# reaction_wheel_board.net
KiCad netlist of a schematic drawn in EAGLE
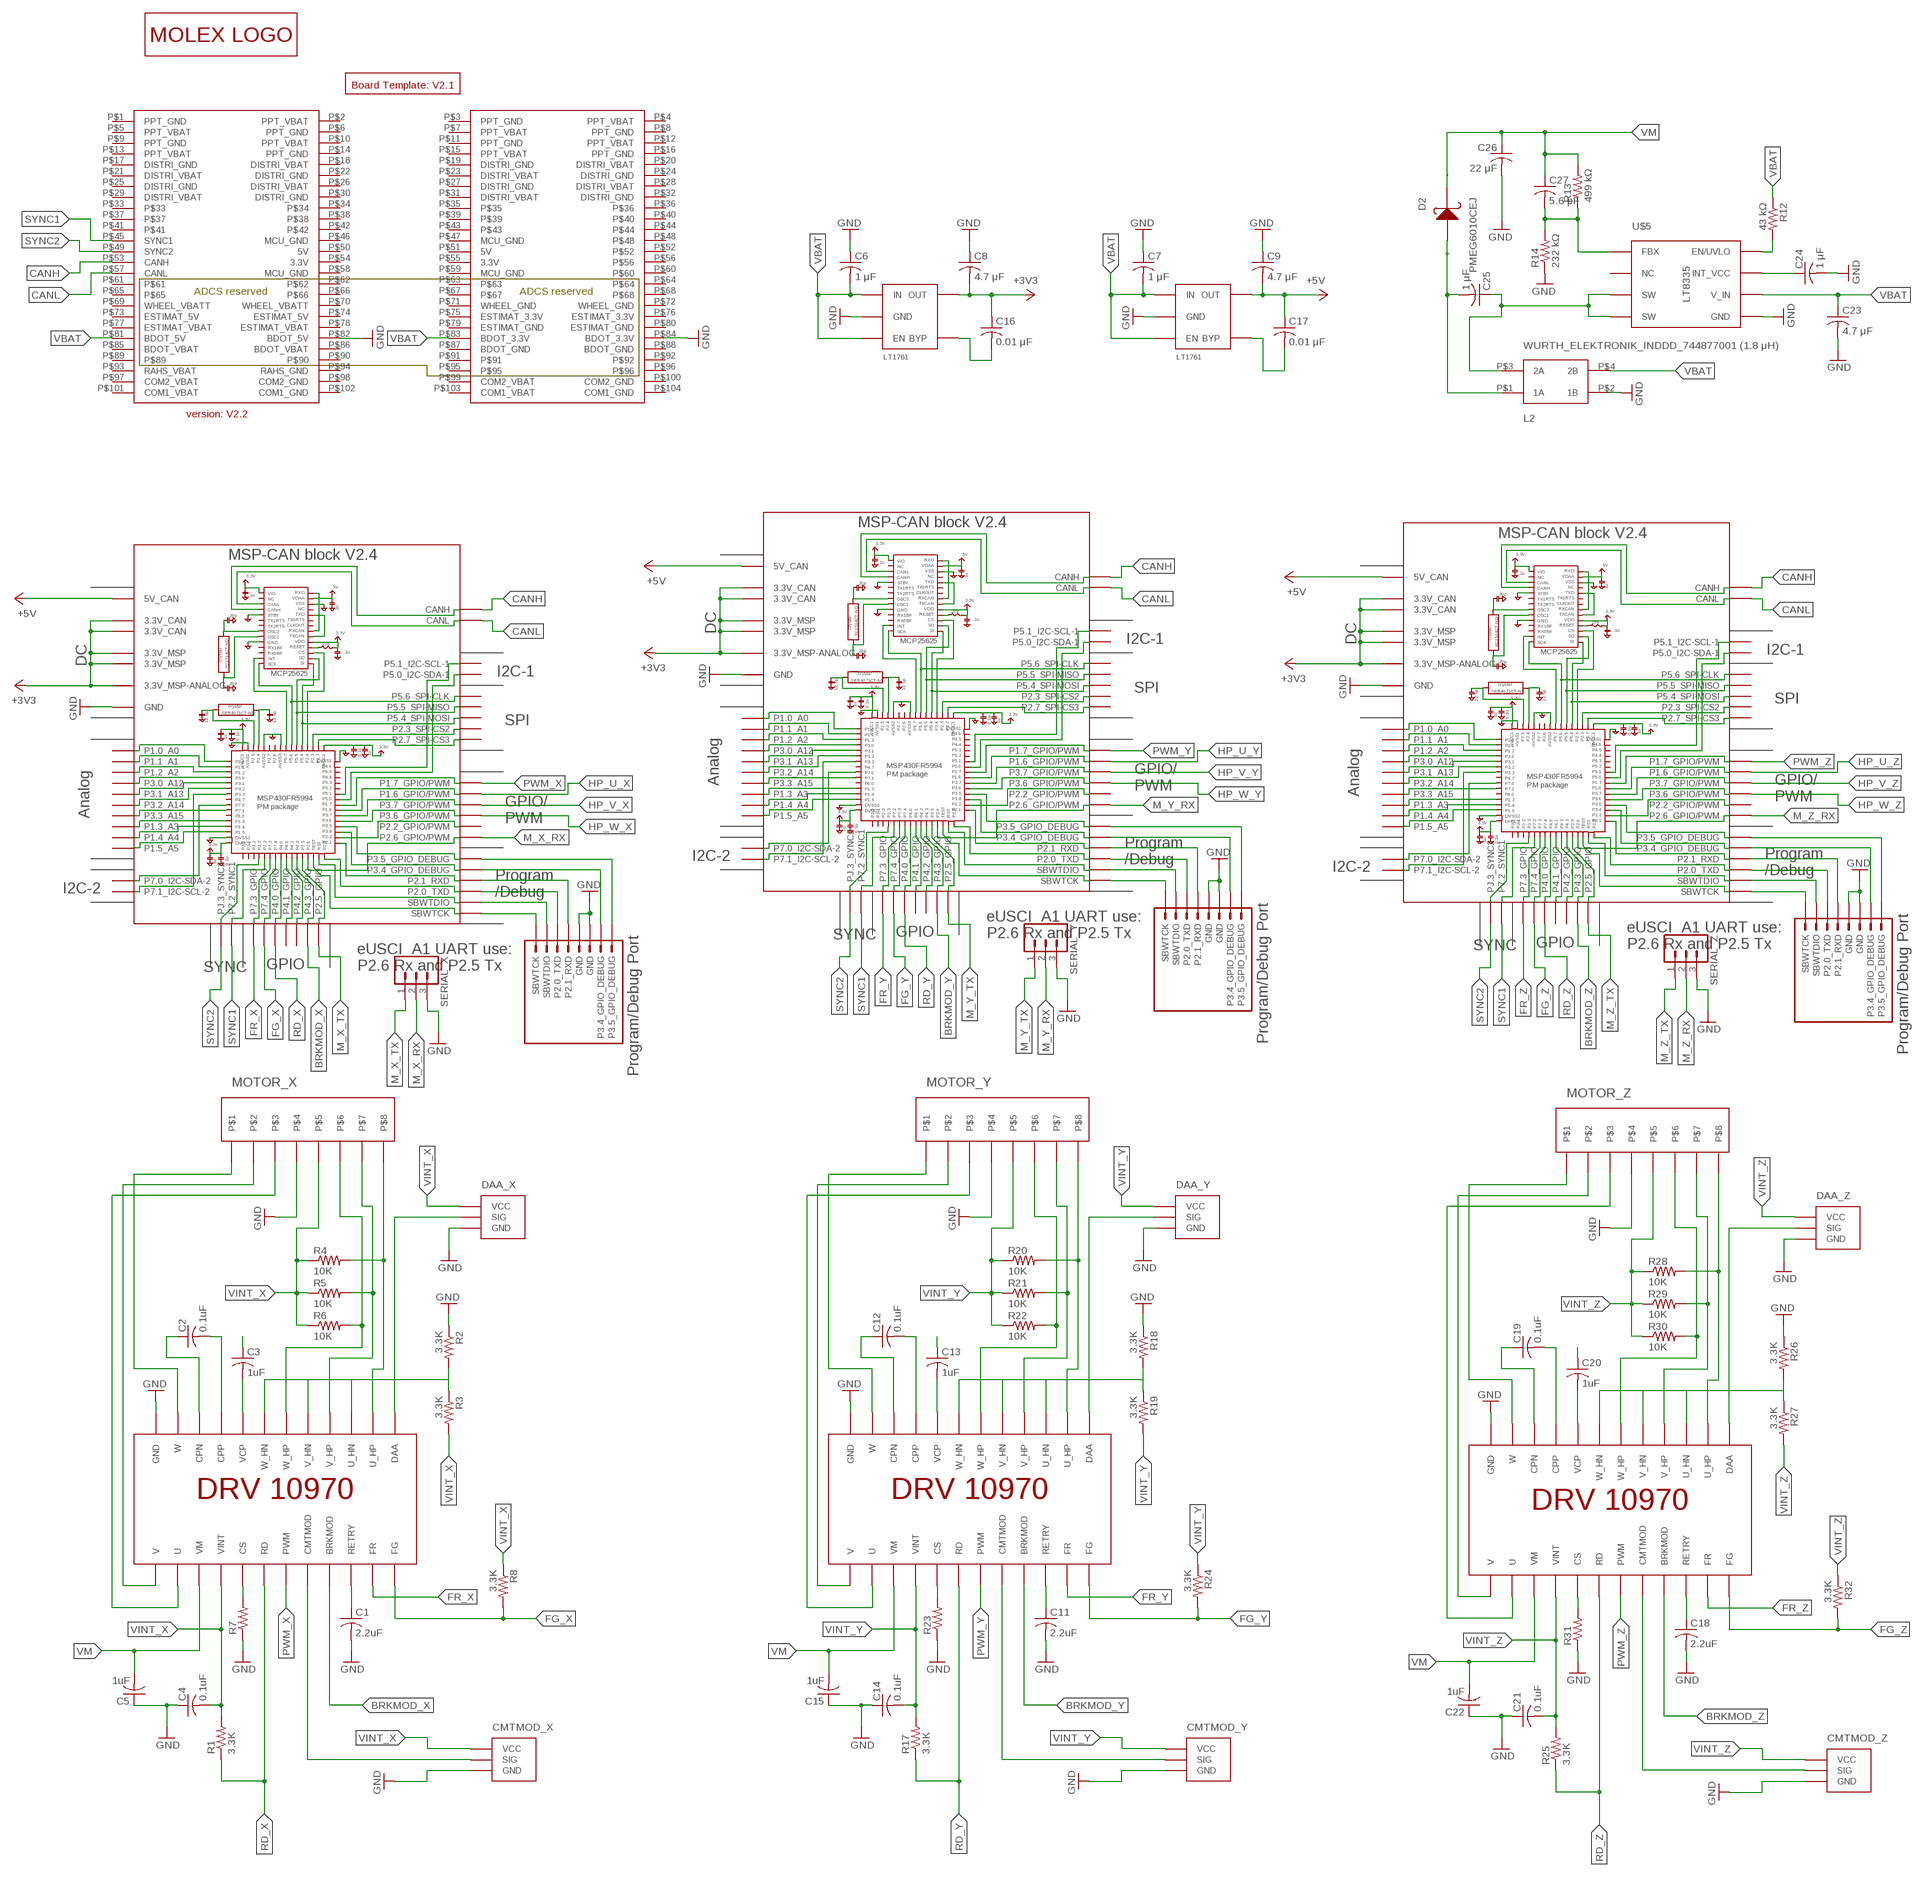
[diagram p0: schematic, sheet 1]

(export (version "E")
  (design (tool "Eeschema 10.0.6"))
  (components
    (comp (ref "C1")
      (value "2.2uF")
      (footprint "eagle-import:C1206")
      (libsource (lib "eagle-import") (part "C-USC1206"))
    )
    (comp (ref "C2")
      (value "0.1uF")
      (footprint "eagle-import:C0805")
      (libsource (lib "eagle-import") (part "C-USC0805"))
    )
    (comp (ref "C3")
      (value "1uF")
      (footprint "eagle-import:C1206")
      (libsource (lib "eagle-import") (part "C-USC1206"))
    )
    (comp (ref "C4")
      (value "0.1uF")
      (footprint "eagle-import:C0805")
      (libsource (lib "eagle-import") (part "C-USC0805"))
    )
    (comp (ref "C5")
      (value "1uF")
      (footprint "eagle-import:C1206")
      (libsource (lib "eagle-import") (part "C-USC1206"))
    )
    (comp (ref "C6")
      (value "1 μF")
      (footprint "eagle-import:C0805")
      (libsource (lib "eagle-import") (part "C-USC0805"))
    )
    (comp (ref "C7")
      (value "1 μF")
      (footprint "eagle-import:C0805")
      (libsource (lib "eagle-import") (part "C-USC0805"))
    )
    (comp (ref "C8")
      (value "4.7 μF")
      (footprint "eagle-import:C0805")
      (libsource (lib "eagle-import") (part "C-USC0805"))
    )
    (comp (ref "C9")
      (value "4.7 μF")
      (footprint "eagle-import:C0805")
      (libsource (lib "eagle-import") (part "C-USC0805"))
    )
    (comp (ref "C11")
      (value "2.2uF")
      (footprint "eagle-import:C1206")
      (libsource (lib "eagle-import") (part "C-USC1206"))
    )
    (comp (ref "C12")
      (value "0.1uF")
      (footprint "eagle-import:C0805")
      (libsource (lib "eagle-import") (part "C-USC0805"))
    )
    (comp (ref "C13")
      (value "1uF")
      (footprint "eagle-import:C1206")
      (libsource (lib "eagle-import") (part "C-USC1206"))
    )
    (comp (ref "C14")
      (value "0.1uF")
      (footprint "eagle-import:C0805")
      (libsource (lib "eagle-import") (part "C-USC0805"))
    )
    (comp (ref "C15")
      (value "1uF")
      (footprint "eagle-import:C1206")
      (libsource (lib "eagle-import") (part "C-USC1206"))
    )
    (comp (ref "C16")
      (value "0.01 μF")
      (footprint "eagle-import:C0805")
      (libsource (lib "eagle-import") (part "C-USC0805"))
    )
    (comp (ref "C17")
      (value "0.01 μF")
      (footprint "eagle-import:C0805")
      (libsource (lib "eagle-import") (part "C-USC0805"))
    )
    (comp (ref "C18")
      (value "2.2uF")
      (footprint "eagle-import:C1206")
      (libsource (lib "eagle-import") (part "C-USC1206"))
    )
    (comp (ref "C19")
      (value "0.1uF")
      (footprint "eagle-import:C0805")
      (libsource (lib "eagle-import") (part "C-USC0805"))
    )
    (comp (ref "C20")
      (value "1uF")
      (footprint "eagle-import:C1206")
      (libsource (lib "eagle-import") (part "C-USC1206"))
    )
    (comp (ref "C21")
      (value "0.1uF")
      (footprint "eagle-import:C0805")
      (libsource (lib "eagle-import") (part "C-USC0805"))
    )
    (comp (ref "C22")
      (value "1uF")
      (footprint "eagle-import:C1206")
      (libsource (lib "eagle-import") (part "C-USC1206"))
    )
    (comp (ref "C23")
      (value "4.7 μF")
      (footprint "eagle-import:C0805")
      (libsource (lib "eagle-import") (part "C-USC0805"))
    )
    (comp (ref "C24")
      (value "1 μF")
      (footprint "eagle-import:C0805")
      (libsource (lib "eagle-import") (part "C-USC0805"))
    )
    (comp (ref "C25")
      (value "1 μF")
      (footprint "eagle-import:C0805")
      (libsource (lib "eagle-import") (part "C-USC0805"))
    )
    (comp (ref "C26")
      (value "22 μF")
      (footprint "eagle-import:C0805")
      (libsource (lib "eagle-import") (part "C-USC0805"))
    )
    (comp (ref "C27")
      (value "5.6 pF")
      (footprint "eagle-import:C0805")
      (libsource (lib "eagle-import") (part "C-USC0805"))
    )
    (comp (ref "CMTMOD_X")
      (value "0_OHM_JUMPER")
      (footprint "eagle-import:0_OHM_JUMPER")
      (libsource (lib "eagle-import") (part "0_OHM_JUMPER"))
    )
    (comp (ref "CMTMOD_Y")
      (value "0_OHM_JUMPER")
      (footprint "eagle-import:0_OHM_JUMPER")
      (libsource (lib "eagle-import") (part "0_OHM_JUMPER"))
    )
    (comp (ref "CMTMOD_Z")
      (value "0_OHM_JUMPER")
      (footprint "eagle-import:0_OHM_JUMPER")
      (libsource (lib "eagle-import") (part "0_OHM_JUMPER"))
    )
    (comp (ref "D2")
      (value "PMEG6010CEJ")
      (footprint "eagle-import:SC-90")
      (libsource (lib "eagle-import") (part "PMEG6010CEJ"))
    )
    (comp (ref "DAA_X")
      (value "0_OHM_JUMPER")
      (footprint "eagle-import:0_OHM_JUMPER")
      (libsource (lib "eagle-import") (part "0_OHM_JUMPER"))
    )
    (comp (ref "DAA_Y")
      (value "0_OHM_JUMPER")
      (footprint "eagle-import:0_OHM_JUMPER")
      (libsource (lib "eagle-import") (part "0_OHM_JUMPER"))
    )
    (comp (ref "DAA_Z")
      (value "0_OHM_JUMPER")
      (footprint "eagle-import:0_OHM_JUMPER")
      (libsource (lib "eagle-import") (part "0_OHM_JUMPER"))
    )
    (comp (ref "L2")
      (value "WURTH_ELEKTRONIK_INDDD_744877001 (1.8 μH)")
      (footprint "eagle-import:WURTH_ELEKTRONIK_INDDD_744877001")
      (libsource (lib "eagle-import") (part "WURTH_ELEKTRONIK_INDDD_744877001"))
    )
    (comp (ref "LDO_3V3")
      (value "LINEAR_LDO_LT1761-X")
      (footprint "eagle-import:SOT-23-5")
      (libsource (lib "eagle-import") (part "LINEAR_LDO_LT1761-X"))
    )
    (comp (ref "LDO_5V")
      (value "LINEAR_LDO_LT1761-X")
      (footprint "eagle-import:SOT-23-5")
      (libsource (lib "eagle-import") (part "LINEAR_LDO_LT1761-X"))
    )
    (comp (ref "MOTOR_X")
      (value "PICOLOCK_8")
      (footprint "eagle-import:PICOLOCK_8")
      (libsource (lib "eagle-import") (part "PICOLOCK_8"))
    )
    (comp (ref "MOTOR_Y")
      (value "PICOLOCK_8")
      (footprint "eagle-import:PICOLOCK_8")
      (libsource (lib "eagle-import") (part "PICOLOCK_8"))
    )
    (comp (ref "MOTOR_Z")
      (value "PICOLOCK_8")
      (footprint "eagle-import:PICOLOCK_8")
      (libsource (lib "eagle-import") (part "PICOLOCK_8"))
    )
    (comp (ref "R1")
      (value "3.3K")
      (footprint "eagle-import:R0805")
      (libsource (lib "eagle-import") (part "R-US_R0805"))
    )
    (comp (ref "R2")
      (value "3.3K")
      (footprint "eagle-import:R0805")
      (libsource (lib "eagle-import") (part "R-US_R0805"))
    )
    (comp (ref "R3")
      (value "3.3K")
      (footprint "eagle-import:R0805")
      (libsource (lib "eagle-import") (part "R-US_R0805"))
    )
    (comp (ref "R4")
      (value "10K")
      (footprint "eagle-import:R0805")
      (libsource (lib "eagle-import") (part "R-US_R0805"))
    )
    (comp (ref "R5")
      (value "10K")
      (footprint "eagle-import:R0805")
      (libsource (lib "eagle-import") (part "R-US_R0805"))
    )
    (comp (ref "R6")
      (value "10K")
      (footprint "eagle-import:R0805")
      (libsource (lib "eagle-import") (part "R-US_R0805"))
    )
    (comp (ref "R7")
      (value "R-US_R0805")
      (footprint "eagle-import:R0805")
      (libsource (lib "eagle-import") (part "R-US_R0805"))
    )
    (comp (ref "R8")
      (value "3.3K")
      (footprint "eagle-import:R0805")
      (libsource (lib "eagle-import") (part "R-US_R0805"))
    )
    (comp (ref "R12")
      (value "43 kΩ")
      (footprint "eagle-import:R0805")
      (libsource (lib "eagle-import") (part "R-US_R0805"))
    )
    (comp (ref "R13")
      (value "499 kΩ")
      (footprint "eagle-import:R0805")
      (libsource (lib "eagle-import") (part "R-US_R0805"))
    )
    (comp (ref "R14")
      (value "232 kΩ")
      (footprint "eagle-import:R0805")
      (libsource (lib "eagle-import") (part "R-US_R0805"))
    )
    (comp (ref "R17")
      (value "3.3K")
      (footprint "eagle-import:R0805")
      (libsource (lib "eagle-import") (part "R-US_R0805"))
    )
    (comp (ref "R18")
      (value "3.3K")
      (footprint "eagle-import:R0805")
      (libsource (lib "eagle-import") (part "R-US_R0805"))
    )
    (comp (ref "R19")
      (value "3.3K")
      (footprint "eagle-import:R0805")
      (libsource (lib "eagle-import") (part "R-US_R0805"))
    )
    (comp (ref "R20")
      (value "10K")
      (footprint "eagle-import:R0805")
      (libsource (lib "eagle-import") (part "R-US_R0805"))
    )
    (comp (ref "R21")
      (value "10K")
      (footprint "eagle-import:R0805")
      (libsource (lib "eagle-import") (part "R-US_R0805"))
    )
    (comp (ref "R22")
      (value "10K")
      (footprint "eagle-import:R0805")
      (libsource (lib "eagle-import") (part "R-US_R0805"))
    )
    (comp (ref "R23")
      (value "R-US_R0805")
      (footprint "eagle-import:R0805")
      (libsource (lib "eagle-import") (part "R-US_R0805"))
    )
    (comp (ref "R24")
      (value "3.3K")
      (footprint "eagle-import:R0805")
      (libsource (lib "eagle-import") (part "R-US_R0805"))
    )
    (comp (ref "R25")
      (value "3.3K")
      (footprint "eagle-import:R0805")
      (libsource (lib "eagle-import") (part "R-US_R0805"))
    )
    (comp (ref "R26")
      (value "3.3K")
      (footprint "eagle-import:R0805")
      (libsource (lib "eagle-import") (part "R-US_R0805"))
    )
    (comp (ref "R27")
      (value "3.3K")
      (footprint "eagle-import:R0805")
      (libsource (lib "eagle-import") (part "R-US_R0805"))
    )
    (comp (ref "R28")
      (value "10K")
      (footprint "eagle-import:R0805")
      (libsource (lib "eagle-import") (part "R-US_R0805"))
    )
    (comp (ref "R29")
      (value "10K")
      (footprint "eagle-import:R0805")
      (libsource (lib "eagle-import") (part "R-US_R0805"))
    )
    (comp (ref "R30")
      (value "10K")
      (footprint "eagle-import:R0805")
      (libsource (lib "eagle-import") (part "R-US_R0805"))
    )
    (comp (ref "R31")
      (value "R-US_R0805")
      (footprint "eagle-import:R0805")
      (libsource (lib "eagle-import") (part "R-US_R0805"))
    )
    (comp (ref "R32")
      (value "3.3K")
      (footprint "eagle-import:R0805")
      (libsource (lib "eagle-import") (part "R-US_R0805"))
    )
    (comp (ref "SERIAL_X")
      (value "CONN_03LOCK")
      (footprint "eagle-import:1X03_LOCK")
      (libsource (lib "eagle-import") (part "CONN_03LOCK"))
    )
    (comp (ref "SERIAL_Y")
      (value "CONN_03LOCK")
      (footprint "eagle-import:1X03_LOCK")
      (libsource (lib "eagle-import") (part "CONN_03LOCK"))
    )
    (comp (ref "SERIAL_Z")
      (value "CONN_03LOCK")
      (footprint "eagle-import:1X03_LOCK")
      (libsource (lib "eagle-import") (part "CONN_03LOCK"))
    )
    (comp (ref "U$1")
      (value "BOARD_TEMPLATE")
      (footprint "eagle-import:BOARD_TEMPLATE")
      (libsource (lib "eagle-import") (part "BOARD_TEMPLATE"))
    )
    (comp (ref "U$2")
      (value "PC104_CONNECTOR")
      (footprint "eagle-import:PC104_CONNECTOR")
      (libsource (lib "eagle-import") (part "PC104_CONNECTOR"))
    )
    (comp (ref "U$3")
      (value "MSP-CAN_BLOCK")
      (footprint "eagle-import:MSP-CAN_BLOCK")
      (libsource (lib "eagle-import") (part "MSP-CAN_BLOCK"))
    )
    (comp (ref "U$4")
      (value "PROGRAM/DEBUG_PORT")
      (footprint "eagle-import:1X08_CONNECTOR")
      (libsource (lib "eagle-import") (part "PROGRAM/DEBUG_PORT"))
    )
    (comp (ref "U$5")
      (value "LT8335")
      (footprint "eagle-import:DDB")
      (libsource (lib "eagle-import") (part "LT8335"))
    )
    (comp (ref "U$7")
      (value "DRV10970")
      (footprint "eagle-import:DRV10970")
      (libsource (lib "eagle-import") (part "DRV10970"))
    )
    (comp (ref "U$8")
      (value "LOGO_MOLEX")
      (footprint "eagle-import:LOGO_MOLEX")
      (libsource (lib "eagle-import") (part "LOGO_MOLEX"))
    )
    (comp (ref "U$10")
      (value "MSP-CAN_BLOCK")
      (footprint "eagle-import:MSP-CAN_BLOCK")
      (libsource (lib "eagle-import") (part "MSP-CAN_BLOCK"))
    )
    (comp (ref "U$11")
      (value "PROGRAM/DEBUG_PORT")
      (footprint "eagle-import:1X08_CONNECTOR")
      (libsource (lib "eagle-import") (part "PROGRAM/DEBUG_PORT"))
    )
    (comp (ref "U$12")
      (value "DRV10970")
      (footprint "eagle-import:DRV10970")
      (libsource (lib "eagle-import") (part "DRV10970"))
    )
    (comp (ref "U$13")
      (value "MSP-CAN_BLOCK")
      (footprint "eagle-import:MSP-CAN_BLOCK")
      (libsource (lib "eagle-import") (part "MSP-CAN_BLOCK"))
    )
    (comp (ref "U$14")
      (value "PROGRAM/DEBUG_PORT")
      (footprint "eagle-import:1X08_CONNECTOR")
      (libsource (lib "eagle-import") (part "PROGRAM/DEBUG_PORT"))
    )
    (comp (ref "U$15")
      (value "DRV10970")
      (footprint "eagle-import:DRV10970")
      (libsource (lib "eagle-import") (part "DRV10970"))
    )
  )
  (nets
    (net (code "1") (name "+3V3") (class "Default")
      (node (ref "C16") (pin "1") (pinfunction "1_1") (pintype "passive"))
      (node (ref "C8") (pin "2") (pinfunction "2_2") (pintype "passive"))
      (node (ref "LDO_3V3") (pin "P$5") (pinfunction "OUT_P$5") (pintype "bidirectional"))
      (node (ref "U$10") (pin "3.3V@CAN1") (pinfunction "3.3V_CAN_3.3V@CAN1") (pintype "bidirectional"))
      (node (ref "U$10") (pin "3.3V@CAN2") (pinfunction "3.3V_CAN_3.3V@CAN2") (pintype "bidirectional"))
      (node (ref "U$10") (pin "3.3V@MSP1") (pinfunction "3.3V_MSP_3.3V@MSP1") (pintype "bidirectional"))
      (node (ref "U$10") (pin "3.3V@MSP2") (pinfunction "3.3V_MSP_3.3V@MSP2") (pintype "bidirectional"))
      (node (ref "U$10") (pin "3.3V_ANALOG@MSP2") (pinfunction "3.3V_MSP-ANALOG_3.3V_ANALOG@MSP2") (pintype "bidirectional"))
      (node (ref "U$13") (pin "3.3V@CAN1") (pinfunction "3.3V_CAN_3.3V@CAN1") (pintype "bidirectional"))
      (node (ref "U$13") (pin "3.3V@CAN2") (pinfunction "3.3V_CAN_3.3V@CAN2") (pintype "bidirectional"))
      (node (ref "U$13") (pin "3.3V@MSP1") (pinfunction "3.3V_MSP_3.3V@MSP1") (pintype "bidirectional"))
      (node (ref "U$13") (pin "3.3V@MSP2") (pinfunction "3.3V_MSP_3.3V@MSP2") (pintype "bidirectional"))
      (node (ref "U$13") (pin "3.3V_ANALOG@MSP2") (pinfunction "3.3V_MSP-ANALOG_3.3V_ANALOG@MSP2") (pintype "bidirectional"))
      (node (ref "U$3") (pin "3.3V@CAN1") (pinfunction "3.3V_CAN_3.3V@CAN1") (pintype "bidirectional"))
      (node (ref "U$3") (pin "3.3V@CAN2") (pinfunction "3.3V_CAN_3.3V@CAN2") (pintype "bidirectional"))
      (node (ref "U$3") (pin "3.3V@MSP1") (pinfunction "3.3V_MSP_3.3V@MSP1") (pintype "bidirectional"))
      (node (ref "U$3") (pin "3.3V@MSP2") (pinfunction "3.3V_MSP_3.3V@MSP2") (pintype "bidirectional"))
      (node (ref "U$3") (pin "3.3V_ANALOG@MSP2") (pinfunction "3.3V_MSP-ANALOG_3.3V_ANALOG@MSP2") (pintype "bidirectional"))
    )
    (net (code "2") (name "+5V") (class "Default")
      (node (ref "C17") (pin "1") (pinfunction "1_1") (pintype "passive"))
      (node (ref "C9") (pin "2") (pinfunction "2_2") (pintype "passive"))
      (node (ref "LDO_5V") (pin "P$5") (pinfunction "OUT_P$5") (pintype "bidirectional"))
      (node (ref "U$10") (pin "5V") (pinfunction "5V_CAN_5V") (pintype "bidirectional"))
      (node (ref "U$13") (pin "5V") (pinfunction "5V_CAN_5V") (pintype "bidirectional"))
      (node (ref "U$3") (pin "5V") (pinfunction "5V_CAN_5V") (pintype "bidirectional"))
    )
    (net (code "3") (name "BRKMOD_X") (class "Default")
      (node (ref "U$3") (pin "P4.3_GPIO") (pinfunction "P4.3_GPIO_P4.3_GPIO") (pintype "bidirectional"))
      (node (ref "U$7") (pin "BRKMOD") (pinfunction "BRKMOD_BRKMOD") (pintype "bidirectional"))
    )
    (net (code "4") (name "BRKMOD_Y") (class "Default")
      (node (ref "U$10") (pin "P4.3_GPIO") (pinfunction "P4.3_GPIO_P4.3_GPIO") (pintype "bidirectional"))
      (node (ref "U$12") (pin "BRKMOD") (pinfunction "BRKMOD_BRKMOD") (pintype "bidirectional"))
    )
    (net (code "5") (name "BRKMOD_Z") (class "Default")
      (node (ref "U$13") (pin "P4.3_GPIO") (pinfunction "P4.3_GPIO_P4.3_GPIO") (pintype "bidirectional"))
      (node (ref "U$15") (pin "BRKMOD") (pinfunction "BRKMOD_BRKMOD") (pintype "bidirectional"))
    )
    (net (code "6") (name "CANH") (class "Default")
      (node (ref "U$10") (pin "CANH") (pinfunction "CANH_CANH") (pintype "bidirectional"))
      (node (ref "U$13") (pin "CANH") (pinfunction "CANH_CANH") (pintype "bidirectional"))
      (node (ref "U$2") (pin "P$53") (pinfunction "CANH_P$53") (pintype "bidirectional"))
      (node (ref "U$3") (pin "CANH") (pinfunction "CANH_CANH") (pintype "bidirectional"))
    )
    (net (code "7") (name "CANL") (class "Default")
      (node (ref "U$10") (pin "CANL") (pinfunction "CANL_CANL") (pintype "bidirectional"))
      (node (ref "U$13") (pin "CANL") (pinfunction "CANL_CANL") (pintype "bidirectional"))
      (node (ref "U$2") (pin "P$57") (pinfunction "CANL_P$57") (pintype "bidirectional"))
      (node (ref "U$3") (pin "CANL") (pinfunction "CANL_CANL") (pintype "bidirectional"))
    )
    (net (code "8") (name "FG_X") (class "Default")
      (node (ref "R8") (pin "2") (pinfunction "2_2") (pintype "passive"))
      (node (ref "U$3") (pin "P7.4_GPIO") (pinfunction "P7.4_GPIO_P7.4_GPIO") (pintype "bidirectional"))
      (node (ref "U$7") (pin "FG") (pinfunction "FG_FG") (pintype "bidirectional"))
    )
    (net (code "9") (name "FG_Y") (class "Default")
      (node (ref "R24") (pin "2") (pinfunction "2_2") (pintype "passive"))
      (node (ref "U$10") (pin "P7.4_GPIO") (pinfunction "P7.4_GPIO_P7.4_GPIO") (pintype "bidirectional"))
      (node (ref "U$12") (pin "FG") (pinfunction "FG_FG") (pintype "bidirectional"))
    )
    (net (code "10") (name "FG_Z") (class "Default")
      (node (ref "R32") (pin "2") (pinfunction "2_2") (pintype "passive"))
      (node (ref "U$13") (pin "P7.4_GPIO") (pinfunction "P7.4_GPIO_P7.4_GPIO") (pintype "bidirectional"))
      (node (ref "U$15") (pin "FG") (pinfunction "FG_FG") (pintype "bidirectional"))
    )
    (net (code "11") (name "FR_X") (class "Default")
      (node (ref "U$3") (pin "P7.3_GPIO") (pinfunction "P7.3_GPIO_P7.3_GPIO") (pintype "bidirectional"))
      (node (ref "U$7") (pin "FR") (pinfunction "FR_FR") (pintype "bidirectional"))
    )
    (net (code "12") (name "FR_Y") (class "Default")
      (node (ref "U$10") (pin "P7.3_GPIO") (pinfunction "P7.3_GPIO_P7.3_GPIO") (pintype "bidirectional"))
      (node (ref "U$12") (pin "FR") (pinfunction "FR_FR") (pintype "bidirectional"))
    )
    (net (code "13") (name "FR_Z") (class "Default")
      (node (ref "U$13") (pin "P7.3_GPIO") (pinfunction "P7.3_GPIO_P7.3_GPIO") (pintype "bidirectional"))
      (node (ref "U$15") (pin "FR") (pinfunction "FR_FR") (pintype "bidirectional"))
    )
    (net (code "14") (name "GND") (class "Default")
      (node (ref "C1") (pin "2") (pinfunction "2_2") (pintype "passive"))
      (node (ref "C11") (pin "2") (pinfunction "2_2") (pintype "passive"))
      (node (ref "C13") (pin "1") (pinfunction "1_1") (pintype "passive"))
      (node (ref "C14") (pin "1") (pinfunction "1_1") (pintype "passive"))
      (node (ref "C15") (pin "1") (pinfunction "1_1") (pintype "passive"))
      (node (ref "C18") (pin "2") (pinfunction "2_2") (pintype "passive"))
      (node (ref "C20") (pin "1") (pinfunction "1_1") (pintype "passive"))
      (node (ref "C21") (pin "1") (pinfunction "1_1") (pintype "passive"))
      (node (ref "C22") (pin "1") (pinfunction "1_1") (pintype "passive"))
      (node (ref "C23") (pin "2") (pinfunction "2_2") (pintype "passive"))
      (node (ref "C24") (pin "2") (pinfunction "2_2") (pintype "passive"))
      (node (ref "C26") (pin "2") (pinfunction "2_2") (pintype "passive"))
      (node (ref "C3") (pin "1") (pinfunction "1_1") (pintype "passive"))
      (node (ref "C4") (pin "1") (pinfunction "1_1") (pintype "passive"))
      (node (ref "C5") (pin "1") (pinfunction "1_1") (pintype "passive"))
      (node (ref "C6") (pin "1") (pinfunction "1_1") (pintype "passive"))
      (node (ref "C7") (pin "1") (pinfunction "1_1") (pintype "passive"))
      (node (ref "C8") (pin "1") (pinfunction "1_1") (pintype "passive"))
      (node (ref "C9") (pin "1") (pinfunction "1_1") (pintype "passive"))
      (node (ref "CMTMOD_X") (pin "P$1") (pinfunction "GND_P$1") (pintype "bidirectional"))
      (node (ref "CMTMOD_Y") (pin "P$1") (pinfunction "GND_P$1") (pintype "bidirectional"))
      (node (ref "CMTMOD_Z") (pin "P$1") (pinfunction "GND_P$1") (pintype "bidirectional"))
      (node (ref "DAA_X") (pin "P$1") (pinfunction "GND_P$1") (pintype "bidirectional"))
      (node (ref "DAA_Y") (pin "P$1") (pinfunction "GND_P$1") (pintype "bidirectional"))
      (node (ref "DAA_Z") (pin "P$1") (pinfunction "GND_P$1") (pintype "bidirectional"))
      (node (ref "L2") (pin "P$2") (pinfunction "1B_P$2") (pintype "bidirectional"))
      (node (ref "LDO_3V3") (pin "P$2") (pinfunction "GND_P$2") (pintype "bidirectional"))
      (node (ref "LDO_5V") (pin "P$2") (pinfunction "GND_P$2") (pintype "bidirectional"))
      (node (ref "MOTOR_X") (pin "P$4") (pinfunction "P$4_P$4") (pintype "bidirectional"))
      (node (ref "MOTOR_Y") (pin "P$4") (pinfunction "P$4_P$4") (pintype "bidirectional"))
      (node (ref "MOTOR_Z") (pin "P$4") (pinfunction "P$4_P$4") (pintype "bidirectional"))
      (node (ref "R14") (pin "1") (pinfunction "1_1") (pintype "passive"))
      (node (ref "R18") (pin "1") (pinfunction "1_1") (pintype "passive"))
      (node (ref "R2") (pin "1") (pinfunction "1_1") (pintype "passive"))
      (node (ref "R23") (pin "1") (pinfunction "1_1") (pintype "passive"))
      (node (ref "R26") (pin "1") (pinfunction "1_1") (pintype "passive"))
      (node (ref "R31") (pin "1") (pinfunction "1_1") (pintype "passive"))
      (node (ref "R7") (pin "1") (pinfunction "1_1") (pintype "passive"))
      (node (ref "SERIAL_X") (pin "3") (pinfunction "3_3") (pintype "passive"))
      (node (ref "SERIAL_Y") (pin "3") (pinfunction "3_3") (pintype "passive"))
      (node (ref "SERIAL_Z") (pin "3") (pinfunction "3_3") (pintype "passive"))
      (node (ref "U$10") (pin "GND@1") (pinfunction "GND_GND@1") (pintype "bidirectional"))
      (node (ref "U$10") (pin "GND@10") (pinfunction "GND_GND@10") (pintype "bidirectional"))
      (node (ref "U$10") (pin "GND@11") (pinfunction "GND_GND@11") (pintype "bidirectional"))
      (node (ref "U$10") (pin "GND@12") (pinfunction "GND_GND@12") (pintype "bidirectional"))
      (node (ref "U$10") (pin "GND@13") (pinfunction "GND_GND@13") (pintype "bidirectional"))
      (node (ref "U$10") (pin "GND@14") (pinfunction "GND_GND@14") (pintype "bidirectional"))
      (node (ref "U$10") (pin "GND@15") (pinfunction "GND_GND@15") (pintype "bidirectional"))
      (node (ref "U$10") (pin "GND@16") (pinfunction "GND_GND@16") (pintype "bidirectional"))
      (node (ref "U$10") (pin "GND@17") (pinfunction "GND_GND@17") (pintype "bidirectional"))
      (node (ref "U$10") (pin "GND@2") (pinfunction "GND_GND@2") (pintype "bidirectional"))
      (node (ref "U$10") (pin "GND@26") (pinfunction "GND_GND@26") (pintype "bidirectional"))
      (node (ref "U$10") (pin "GND@3") (pinfunction "GND_GND@3") (pintype "bidirectional"))
      (node (ref "U$10") (pin "GND@4") (pinfunction "GND_GND@4") (pintype "bidirectional"))
      (node (ref "U$10") (pin "GND@5") (pinfunction "GND_GND@5") (pintype "bidirectional"))
      (node (ref "U$10") (pin "GND@7") (pinfunction "GND_GND@7") (pintype "bidirectional"))
      (node (ref "U$10") (pin "GND@8") (pinfunction "GND_GND@8") (pintype "bidirectional"))
      (node (ref "U$10") (pin "GND@9") (pinfunction "GND_GND@9") (pintype "bidirectional"))
      (node (ref "U$11") (pin "5") (pinfunction "GND_5") (pintype "bidirectional"))
      (node (ref "U$11") (pin "6") (pinfunction "GND_6") (pintype "bidirectional"))
      (node (ref "U$12") (pin "GND@1") (pinfunction "GND_GND@1") (pintype "bidirectional"))
      (node (ref "U$12") (pin "GND@2") (pinfunction "GND_GND@2") (pintype "bidirectional"))
      (node (ref "U$13") (pin "GND@1") (pinfunction "GND_GND@1") (pintype "bidirectional"))
      (node (ref "U$13") (pin "GND@10") (pinfunction "GND_GND@10") (pintype "bidirectional"))
      (node (ref "U$13") (pin "GND@11") (pinfunction "GND_GND@11") (pintype "bidirectional"))
      (node (ref "U$13") (pin "GND@12") (pinfunction "GND_GND@12") (pintype "bidirectional"))
      (node (ref "U$13") (pin "GND@13") (pinfunction "GND_GND@13") (pintype "bidirectional"))
      (node (ref "U$13") (pin "GND@14") (pinfunction "GND_GND@14") (pintype "bidirectional"))
      (node (ref "U$13") (pin "GND@15") (pinfunction "GND_GND@15") (pintype "bidirectional"))
      (node (ref "U$13") (pin "GND@16") (pinfunction "GND_GND@16") (pintype "bidirectional"))
      (node (ref "U$13") (pin "GND@17") (pinfunction "GND_GND@17") (pintype "bidirectional"))
      (node (ref "U$13") (pin "GND@2") (pinfunction "GND_GND@2") (pintype "bidirectional"))
      (node (ref "U$13") (pin "GND@26") (pinfunction "GND_GND@26") (pintype "bidirectional"))
      (node (ref "U$13") (pin "GND@3") (pinfunction "GND_GND@3") (pintype "bidirectional"))
      (node (ref "U$13") (pin "GND@4") (pinfunction "GND_GND@4") (pintype "bidirectional"))
      (node (ref "U$13") (pin "GND@5") (pinfunction "GND_GND@5") (pintype "bidirectional"))
      (node (ref "U$13") (pin "GND@7") (pinfunction "GND_GND@7") (pintype "bidirectional"))
      (node (ref "U$13") (pin "GND@8") (pinfunction "GND_GND@8") (pintype "bidirectional"))
      (node (ref "U$13") (pin "GND@9") (pinfunction "GND_GND@9") (pintype "bidirectional"))
      (node (ref "U$14") (pin "5") (pinfunction "GND_5") (pintype "bidirectional"))
      (node (ref "U$14") (pin "6") (pinfunction "GND_6") (pintype "bidirectional"))
      (node (ref "U$15") (pin "GND@1") (pinfunction "GND_GND@1") (pintype "bidirectional"))
      (node (ref "U$15") (pin "GND@2") (pinfunction "GND_GND@2") (pintype "bidirectional"))
      (node (ref "U$2") (pin "P$82") (pinfunction "BDOT_5V_P$82") (pintype "bidirectional"))
      (node (ref "U$2") (pin "P$84") (pinfunction "BDOT_3.3V_P$84") (pintype "bidirectional"))
      (node (ref "U$3") (pin "GND@1") (pinfunction "GND_GND@1") (pintype "bidirectional"))
      (node (ref "U$3") (pin "GND@10") (pinfunction "GND_GND@10") (pintype "bidirectional"))
      (node (ref "U$3") (pin "GND@11") (pinfunction "GND_GND@11") (pintype "bidirectional"))
      (node (ref "U$3") (pin "GND@12") (pinfunction "GND_GND@12") (pintype "bidirectional"))
      (node (ref "U$3") (pin "GND@13") (pinfunction "GND_GND@13") (pintype "bidirectional"))
      (node (ref "U$3") (pin "GND@14") (pinfunction "GND_GND@14") (pintype "bidirectional"))
      (node (ref "U$3") (pin "GND@15") (pinfunction "GND_GND@15") (pintype "bidirectional"))
      (node (ref "U$3") (pin "GND@16") (pinfunction "GND_GND@16") (pintype "bidirectional"))
      (node (ref "U$3") (pin "GND@17") (pinfunction "GND_GND@17") (pintype "bidirectional"))
      (node (ref "U$3") (pin "GND@2") (pinfunction "GND_GND@2") (pintype "bidirectional"))
      (node (ref "U$3") (pin "GND@26") (pinfunction "GND_GND@26") (pintype "bidirectional"))
      (node (ref "U$3") (pin "GND@3") (pinfunction "GND_GND@3") (pintype "bidirectional"))
      (node (ref "U$3") (pin "GND@4") (pinfunction "GND_GND@4") (pintype "bidirectional"))
      (node (ref "U$3") (pin "GND@5") (pinfunction "GND_GND@5") (pintype "bidirectional"))
      (node (ref "U$3") (pin "GND@7") (pinfunction "GND_GND@7") (pintype "bidirectional"))
      (node (ref "U$3") (pin "GND@8") (pinfunction "GND_GND@8") (pintype "bidirectional"))
      (node (ref "U$3") (pin "GND@9") (pinfunction "GND_GND@9") (pintype "bidirectional"))
      (node (ref "U$4") (pin "5") (pinfunction "GND_5") (pintype "bidirectional"))
      (node (ref "U$4") (pin "6") (pinfunction "GND_6") (pintype "bidirectional"))
      (node (ref "U$5") (pin "GND") (pinfunction "GND_GND") (pintype "bidirectional"))
      (node (ref "U$5") (pin "P$5") (pinfunction "GND_P$5") (pintype "bidirectional"))
      (node (ref "U$7") (pin "GND@1") (pinfunction "GND_GND@1") (pintype "bidirectional"))
      (node (ref "U$7") (pin "GND@2") (pinfunction "GND_GND@2") (pintype "bidirectional"))
    )
    (net (code "15") (name "HP_U_X") (class "Default")
      (node (ref "MOTOR_X") (pin "P$8") (pinfunction "P$8_P$8") (pintype "bidirectional"))
      (node (ref "R4") (pin "2") (pinfunction "2_2") (pintype "passive"))
      (node (ref "U$3") (pin "P1.6_GPIO/PWM") (pinfunction "P1.6_GPIO/PWM_P1.6_GPIO/PWM") (pintype "bidirectional"))
      (node (ref "U$7") (pin "U_HP") (pinfunction "U_HP_U_HP") (pintype "bidirectional"))
    )
    (net (code "16") (name "HP_U_Y") (class "Default")
      (node (ref "MOTOR_Y") (pin "P$8") (pinfunction "P$8_P$8") (pintype "bidirectional"))
      (node (ref "R20") (pin "2") (pinfunction "2_2") (pintype "passive"))
      (node (ref "U$10") (pin "P1.6_GPIO/PWM") (pinfunction "P1.6_GPIO/PWM_P1.6_GPIO/PWM") (pintype "bidirectional"))
      (node (ref "U$12") (pin "U_HP") (pinfunction "U_HP_U_HP") (pintype "bidirectional"))
    )
    (net (code "17") (name "HP_U_Z") (class "Default")
      (node (ref "MOTOR_Z") (pin "P$8") (pinfunction "P$8_P$8") (pintype "bidirectional"))
      (node (ref "R28") (pin "2") (pinfunction "2_2") (pintype "passive"))
      (node (ref "U$13") (pin "P1.6_GPIO/PWM") (pinfunction "P1.6_GPIO/PWM_P1.6_GPIO/PWM") (pintype "bidirectional"))
      (node (ref "U$15") (pin "U_HP") (pinfunction "U_HP_U_HP") (pintype "bidirectional"))
    )
    (net (code "18") (name "HP_V_X") (class "Default")
      (node (ref "MOTOR_X") (pin "P$7") (pinfunction "P$7_P$7") (pintype "bidirectional"))
      (node (ref "R5") (pin "2") (pinfunction "2_2") (pintype "passive"))
      (node (ref "U$3") (pin "P3.7_GPIO/PWM") (pinfunction "P3.7_GPIO/PWM_P3.7_GPIO/PWM") (pintype "bidirectional"))
      (node (ref "U$7") (pin "V_HP") (pinfunction "V_HP_V_HP") (pintype "bidirectional"))
    )
    (net (code "19") (name "HP_V_Y") (class "Default")
      (node (ref "MOTOR_Y") (pin "P$7") (pinfunction "P$7_P$7") (pintype "bidirectional"))
      (node (ref "R21") (pin "2") (pinfunction "2_2") (pintype "passive"))
      (node (ref "U$10") (pin "P3.7_GPIO/PWM") (pinfunction "P3.7_GPIO/PWM_P3.7_GPIO/PWM") (pintype "bidirectional"))
      (node (ref "U$12") (pin "V_HP") (pinfunction "V_HP_V_HP") (pintype "bidirectional"))
    )
    (net (code "20") (name "HP_V_Z") (class "Default")
      (node (ref "MOTOR_Z") (pin "P$7") (pinfunction "P$7_P$7") (pintype "bidirectional"))
      (node (ref "R29") (pin "2") (pinfunction "2_2") (pintype "passive"))
      (node (ref "U$13") (pin "P3.7_GPIO/PWM") (pinfunction "P3.7_GPIO/PWM_P3.7_GPIO/PWM") (pintype "bidirectional"))
      (node (ref "U$15") (pin "V_HP") (pinfunction "V_HP_V_HP") (pintype "bidirectional"))
    )
    (net (code "21") (name "HP_W_X") (class "Default")
      (node (ref "MOTOR_X") (pin "P$6") (pinfunction "P$6_P$6") (pintype "bidirectional"))
      (node (ref "R6") (pin "2") (pinfunction "2_2") (pintype "passive"))
      (node (ref "U$3") (pin "P3.6_GPIO/PWM") (pinfunction "P3.6_GPIO/PWM_P3.6_GPIO/PWM") (pintype "bidirectional"))
      (node (ref "U$7") (pin "W_HP") (pinfunction "W_HP_W_HP") (pintype "bidirectional"))
    )
    (net (code "22") (name "HP_W_Y") (class "Default")
      (node (ref "MOTOR_Y") (pin "P$6") (pinfunction "P$6_P$6") (pintype "bidirectional"))
      (node (ref "R22") (pin "2") (pinfunction "2_2") (pintype "passive"))
      (node (ref "U$10") (pin "P3.6_GPIO/PWM") (pinfunction "P3.6_GPIO/PWM_P3.6_GPIO/PWM") (pintype "bidirectional"))
      (node (ref "U$12") (pin "W_HP") (pinfunction "W_HP_W_HP") (pintype "bidirectional"))
    )
    (net (code "23") (name "HP_W_Z") (class "Default")
      (node (ref "MOTOR_Z") (pin "P$6") (pinfunction "P$6_P$6") (pintype "bidirectional"))
      (node (ref "R30") (pin "2") (pinfunction "2_2") (pintype "passive"))
      (node (ref "U$13") (pin "P3.6_GPIO/PWM") (pinfunction "P3.6_GPIO/PWM_P3.6_GPIO/PWM") (pintype "bidirectional"))
      (node (ref "U$15") (pin "W_HP") (pinfunction "W_HP_W_HP") (pintype "bidirectional"))
    )
    (net (code "24") (name "M_X_RX") (class "Default")
      (node (ref "SERIAL_X") (pin "2") (pinfunction "2_2") (pintype "passive"))
      (node (ref "U$3") (pin "P2.6_GPIO/PWM") (pinfunction "P2.6_GPIO/PWM_P2.6_GPIO/PWM") (pintype "bidirectional"))
    )
    (net (code "25") (name "M_X_TX") (class "Default")
      (node (ref "SERIAL_X") (pin "1") (pinfunction "1_1") (pintype "passive"))
      (node (ref "U$3") (pin "P2.5_GPIO") (pinfunction "P2.5_GPIO_P2.5_GPIO") (pintype "bidirectional"))
    )
    (net (code "26") (name "M_Y_RX") (class "Default")
      (node (ref "SERIAL_Y") (pin "2") (pinfunction "2_2") (pintype "passive"))
      (node (ref "U$10") (pin "P2.6_GPIO/PWM") (pinfunction "P2.6_GPIO/PWM_P2.6_GPIO/PWM") (pintype "bidirectional"))
    )
    (net (code "27") (name "M_Y_TX") (class "Default")
      (node (ref "SERIAL_Y") (pin "1") (pinfunction "1_1") (pintype "passive"))
      (node (ref "U$10") (pin "P2.5_GPIO") (pinfunction "P2.5_GPIO_P2.5_GPIO") (pintype "bidirectional"))
    )
    (net (code "28") (name "M_Z_RX") (class "Default")
      (node (ref "SERIAL_Z") (pin "2") (pinfunction "2_2") (pintype "passive"))
      (node (ref "U$13") (pin "P2.6_GPIO/PWM") (pinfunction "P2.6_GPIO/PWM_P2.6_GPIO/PWM") (pintype "bidirectional"))
    )
    (net (code "29") (name "M_Z_TX") (class "Default")
      (node (ref "SERIAL_Z") (pin "1") (pinfunction "1_1") (pintype "passive"))
      (node (ref "U$13") (pin "P2.5_GPIO") (pinfunction "P2.5_GPIO_P2.5_GPIO") (pintype "bidirectional"))
    )
    (net (code "30") (name "Net-(C1-Pad1)") (class "Default")
      (node (ref "C1") (pin "1") (pinfunction "1_1") (pintype "passive"))
      (node (ref "U$7") (pin "RETRY") (pinfunction "RETRY_RETRY") (pintype "bidirectional"))
    )
    (net (code "31") (name "Net-(C2-Pad1)") (class "Default")
      (node (ref "C2") (pin "1") (pinfunction "1_1") (pintype "passive"))
      (node (ref "U$7") (pin "CPN") (pinfunction "CPN_CPN") (pintype "bidirectional"))
    )
    (net (code "32") (name "Net-(C2-Pad2)") (class "Default")
      (node (ref "C2") (pin "2") (pinfunction "2_2") (pintype "passive"))
      (node (ref "U$7") (pin "CPP") (pinfunction "CPP_CPP") (pintype "bidirectional"))
    )
    (net (code "33") (name "Net-(C3-Pad2)") (class "Default")
      (node (ref "C3") (pin "2") (pinfunction "2_2") (pintype "passive"))
      (node (ref "U$7") (pin "VCP") (pinfunction "VCP_VCP") (pintype "bidirectional"))
    )
    (net (code "34") (name "Net-(C11-Pad1)") (class "Default")
      (node (ref "C11") (pin "1") (pinfunction "1_1") (pintype "passive"))
      (node (ref "U$12") (pin "RETRY") (pinfunction "RETRY_RETRY") (pintype "bidirectional"))
    )
    (net (code "35") (name "Net-(C12-Pad1)") (class "Default")
      (node (ref "C12") (pin "1") (pinfunction "1_1") (pintype "passive"))
      (node (ref "U$12") (pin "CPN") (pinfunction "CPN_CPN") (pintype "bidirectional"))
    )
    (net (code "36") (name "Net-(C12-Pad2)") (class "Default")
      (node (ref "C12") (pin "2") (pinfunction "2_2") (pintype "passive"))
      (node (ref "U$12") (pin "CPP") (pinfunction "CPP_CPP") (pintype "bidirectional"))
    )
    (net (code "37") (name "Net-(C13-Pad2)") (class "Default")
      (node (ref "C13") (pin "2") (pinfunction "2_2") (pintype "passive"))
      (node (ref "U$12") (pin "VCP") (pinfunction "VCP_VCP") (pintype "bidirectional"))
    )
    (net (code "38") (name "Net-(C18-Pad1)") (class "Default")
      (node (ref "C18") (pin "1") (pinfunction "1_1") (pintype "passive"))
      (node (ref "U$15") (pin "RETRY") (pinfunction "RETRY_RETRY") (pintype "bidirectional"))
    )
    (net (code "39") (name "Net-(C19-Pad1)") (class "Default")
      (node (ref "C19") (pin "1") (pinfunction "1_1") (pintype "passive"))
      (node (ref "U$15") (pin "CPN") (pinfunction "CPN_CPN") (pintype "bidirectional"))
    )
    (net (code "40") (name "Net-(C19-Pad2)") (class "Default")
      (node (ref "C19") (pin "2") (pinfunction "2_2") (pintype "passive"))
      (node (ref "U$15") (pin "CPP") (pinfunction "CPP_CPP") (pintype "bidirectional"))
    )
    (net (code "41") (name "Net-(C20-Pad2)") (class "Default")
      (node (ref "C20") (pin "2") (pinfunction "2_2") (pintype "passive"))
      (node (ref "U$15") (pin "VCP") (pinfunction "VCP_VCP") (pintype "bidirectional"))
    )
    (net (code "42") (name "Net-(CMTMOD_X-SIG)") (class "Default")
      (node (ref "CMTMOD_X") (pin "P$2") (pinfunction "SIG_P$2") (pintype "bidirectional"))
      (node (ref "U$7") (pin "CMTMOD") (pinfunction "CMTMOD_CMTMOD") (pintype "bidirectional"))
    )
    (net (code "43") (name "Net-(CMTMOD_Y-SIG)") (class "Default")
      (node (ref "CMTMOD_Y") (pin "P$2") (pinfunction "SIG_P$2") (pintype "bidirectional"))
      (node (ref "U$12") (pin "CMTMOD") (pinfunction "CMTMOD_CMTMOD") (pintype "bidirectional"))
    )
    (net (code "44") (name "Net-(CMTMOD_Z-SIG)") (class "Default")
      (node (ref "CMTMOD_Z") (pin "P$2") (pinfunction "SIG_P$2") (pintype "bidirectional"))
      (node (ref "U$15") (pin "CMTMOD") (pinfunction "CMTMOD_CMTMOD") (pintype "bidirectional"))
    )
    (net (code "45") (name "Net-(D2-+)") (class "Default")
      (node (ref "C25") (pin "2") (pinfunction "2_2") (pintype "passive"))
      (node (ref "D2") (pin "P$1") (pinfunction "+_P$1") (pintype "bidirectional"))
      (node (ref "L2") (pin "P$1") (pinfunction "1A_P$1") (pintype "bidirectional"))
    )
    (net (code "46") (name "Net-(DAA_X-SIG)") (class "Default")
      (node (ref "DAA_X") (pin "P$2") (pinfunction "SIG_P$2") (pintype "bidirectional"))
      (node (ref "U$7") (pin "DAA") (pinfunction "DAA_DAA") (pintype "bidirectional"))
    )
    (net (code "47") (name "Net-(DAA_Y-SIG)") (class "Default")
      (node (ref "DAA_Y") (pin "P$2") (pinfunction "SIG_P$2") (pintype "bidirectional"))
      (node (ref "U$12") (pin "DAA") (pinfunction "DAA_DAA") (pintype "bidirectional"))
    )
    (net (code "48") (name "Net-(DAA_Z-SIG)") (class "Default")
      (node (ref "DAA_Z") (pin "P$2") (pinfunction "SIG_P$2") (pintype "bidirectional"))
      (node (ref "U$15") (pin "DAA") (pinfunction "DAA_DAA") (pintype "bidirectional"))
    )
    (net (code "49") (name "Net-(L2-2A)") (class "Default")
      (node (ref "C25") (pin "1") (pinfunction "1_1") (pintype "passive"))
      (node (ref "L2") (pin "P$3") (pinfunction "2A_P$3") (pintype "bidirectional"))
      (node (ref "U$5") (pin "P$3") (pinfunction "SW_P$3") (pintype "bidirectional"))
      (node (ref "U$5") (pin "P$4") (pinfunction "SW_P$4") (pintype "bidirectional"))
    )
    (net (code "50") (name "Net-(LDO_3V3-BYP)") (class "Default")
      (node (ref "C16") (pin "2") (pinfunction "2_2") (pintype "passive"))
      (node (ref "LDO_3V3") (pin "P$4") (pinfunction "BYP_P$4") (pintype "bidirectional"))
    )
    (net (code "51") (name "Net-(LDO_5V-BYP)") (class "Default")
      (node (ref "C17") (pin "2") (pinfunction "2_2") (pintype "passive"))
      (node (ref "LDO_5V") (pin "P$4") (pinfunction "BYP_P$4") (pintype "bidirectional"))
    )
    (net (code "52") (name "Net-(MOTOR_X-PadP$1)") (class "Default")
      (node (ref "MOTOR_X") (pin "P$1") (pinfunction "P$1_P$1") (pintype "bidirectional"))
      (node (ref "U$7") (pin "W") (pinfunction "W_W") (pintype "bidirectional"))
    )
    (net (code "53") (name "Net-(MOTOR_X-PadP$2)") (class "Default")
      (node (ref "MOTOR_X") (pin "P$2") (pinfunction "P$2_P$2") (pintype "bidirectional"))
      (node (ref "U$7") (pin "V") (pinfunction "V_V") (pintype "bidirectional"))
    )
    (net (code "54") (name "Net-(MOTOR_X-PadP$3)") (class "Default")
      (node (ref "MOTOR_X") (pin "P$3") (pinfunction "P$3_P$3") (pintype "bidirectional"))
      (node (ref "U$7") (pin "U") (pinfunction "U_U") (pintype "bidirectional"))
    )
    (net (code "55") (name "Net-(MOTOR_Y-PadP$1)") (class "Default")
      (node (ref "MOTOR_Y") (pin "P$1") (pinfunction "P$1_P$1") (pintype "bidirectional"))
      (node (ref "U$12") (pin "W") (pinfunction "W_W") (pintype "bidirectional"))
    )
    (net (code "56") (name "Net-(MOTOR_Y-PadP$2)") (class "Default")
      (node (ref "MOTOR_Y") (pin "P$2") (pinfunction "P$2_P$2") (pintype "bidirectional"))
      (node (ref "U$12") (pin "V") (pinfunction "V_V") (pintype "bidirectional"))
    )
    (net (code "57") (name "Net-(MOTOR_Y-PadP$3)") (class "Default")
      (node (ref "MOTOR_Y") (pin "P$3") (pinfunction "P$3_P$3") (pintype "bidirectional"))
      (node (ref "U$12") (pin "U") (pinfunction "U_U") (pintype "bidirectional"))
    )
    (net (code "58") (name "Net-(MOTOR_Z-PadP$1)") (class "Default")
      (node (ref "MOTOR_Z") (pin "P$1") (pinfunction "P$1_P$1") (pintype "bidirectional"))
      (node (ref "U$15") (pin "W") (pinfunction "W_W") (pintype "bidirectional"))
    )
    (net (code "59") (name "Net-(MOTOR_Z-PadP$2)") (class "Default")
      (node (ref "MOTOR_Z") (pin "P$2") (pinfunction "P$2_P$2") (pintype "bidirectional"))
      (node (ref "U$15") (pin "V") (pinfunction "V_V") (pintype "bidirectional"))
    )
    (net (code "60") (name "Net-(MOTOR_Z-PadP$3)") (class "Default")
      (node (ref "MOTOR_Z") (pin "P$3") (pinfunction "P$3_P$3") (pintype "bidirectional"))
      (node (ref "U$15") (pin "U") (pinfunction "U_U") (pintype "bidirectional"))
    )
    (net (code "61") (name "Net-(R2-Pad2)") (class "Default")
      (node (ref "R2") (pin "2") (pinfunction "2_2") (pintype "passive"))
      (node (ref "R3") (pin "1") (pinfunction "1_1") (pintype "passive"))
      (node (ref "U$7") (pin "U_HN") (pinfunction "U_HN_U_HN") (pintype "bidirectional"))
      (node (ref "U$7") (pin "V_HN") (pinfunction "V_HN_V_HN") (pintype "bidirectional"))
      (node (ref "U$7") (pin "W_HN") (pinfunction "W_HN_W_HN") (pintype "bidirectional"))
    )
    (net (code "62") (name "Net-(R7-Pad2)") (class "Default")
      (node (ref "R7") (pin "2") (pinfunction "2_2") (pintype "passive"))
      (node (ref "U$7") (pin "CS") (pinfunction "CS_CS") (pintype "bidirectional"))
    )
    (net (code "63") (name "Net-(R18-Pad2)") (class "Default")
      (node (ref "R18") (pin "2") (pinfunction "2_2") (pintype "passive"))
      (node (ref "R19") (pin "1") (pinfunction "1_1") (pintype "passive"))
      (node (ref "U$12") (pin "U_HN") (pinfunction "U_HN_U_HN") (pintype "bidirectional"))
      (node (ref "U$12") (pin "V_HN") (pinfunction "V_HN_V_HN") (pintype "bidirectional"))
      (node (ref "U$12") (pin "W_HN") (pinfunction "W_HN_W_HN") (pintype "bidirectional"))
    )
    (net (code "64") (name "Net-(R23-Pad2)") (class "Default")
      (node (ref "R23") (pin "2") (pinfunction "2_2") (pintype "passive"))
      (node (ref "U$12") (pin "CS") (pinfunction "CS_CS") (pintype "bidirectional"))
    )
    (net (code "65") (name "Net-(R26-Pad2)") (class "Default")
      (node (ref "R26") (pin "2") (pinfunction "2_2") (pintype "passive"))
      (node (ref "R27") (pin "1") (pinfunction "1_1") (pintype "passive"))
      (node (ref "U$15") (pin "U_HN") (pinfunction "U_HN_U_HN") (pintype "bidirectional"))
      (node (ref "U$15") (pin "V_HN") (pinfunction "V_HN_V_HN") (pintype "bidirectional"))
      (node (ref "U$15") (pin "W_HN") (pinfunction "W_HN_W_HN") (pintype "bidirectional"))
    )
    (net (code "66") (name "Net-(R31-Pad2)") (class "Default")
      (node (ref "R31") (pin "2") (pinfunction "2_2") (pintype "passive"))
      (node (ref "U$15") (pin "CS") (pinfunction "CS_CS") (pintype "bidirectional"))
    )
    (net (code "67") (name "Net-(U$3-PadSBWTCK)") (class "Default")
      (node (ref "U$3") (pin "SBWTCK") (pinfunction "SBWTCK_SBWTCK") (pintype "bidirectional"))
      (node (ref "U$4") (pin "SBWTCK") (pinfunction "SBWTCK_SBWTCK") (pintype "bidirectional"))
    )
    (net (code "68") (name "Net-(U$4-P2.0_TXD)") (class "Default")
      (node (ref "U$3") (pin "P2.0_TXD") (pinfunction "P2.0_TXD_P2.0_TXD") (pintype "bidirectional"))
      (node (ref "U$4") (pin "3") (pinfunction "P2.0_TXD_3") (pintype "bidirectional"))
    )
    (net (code "69") (name "Net-(U$4-P2.1_RXD)") (class "Default")
      (node (ref "U$3") (pin "P2.1_RXD") (pinfunction "P2.1_RXD_P2.1_RXD") (pintype "bidirectional"))
      (node (ref "U$4") (pin "4") (pinfunction "P2.1_RXD_4") (pintype "bidirectional"))
    )
    (net (code "70") (name "Net-(U$4-P3.4_GPIO_DEBUG)") (class "Default")
      (node (ref "U$3") (pin "P3.4_GPIO_DEBUG") (pinfunction "P3.4_GPIO_DEBUG_P3.4_GPIO_DEBUG") (pintype "bidirectional"))
      (node (ref "U$4") (pin "7") (pinfunction "P3.4_GPIO_DEBUG_7") (pintype "bidirectional"))
    )
    (net (code "71") (name "Net-(U$4-P3.5_GPIO_DEBUG)") (class "Default")
      (node (ref "U$3") (pin "P3.5_GPIO_DEBUG") (pinfunction "P3.5_GPIO_DEBUG_P3.5_GPIO_DEBUG") (pintype "bidirectional"))
      (node (ref "U$4") (pin "8") (pinfunction "P3.5_GPIO_DEBUG_8") (pintype "bidirectional"))
    )
    (net (code "72") (name "Net-(U$4-SBWTDIO)") (class "Default")
      (node (ref "U$3") (pin "SBWTDIO") (pinfunction "SBWTDIO_SBWTDIO") (pintype "bidirectional"))
      (node (ref "U$4") (pin "2") (pinfunction "SBWTDIO_2") (pintype "bidirectional"))
    )
    (net (code "73") (name "Net-(U$5-EN{slash}UVLO)") (class "Default")
      (node (ref "R12") (pin "2") (pinfunction "2_2") (pintype "passive"))
      (node (ref "U$5") (pin "P$8") (pinfunction "EN/UVLO_P$8") (pintype "bidirectional"))
    )
    (net (code "74") (name "Net-(U$5-FBX)") (class "Default")
      (node (ref "C27") (pin "2") (pinfunction "2_2") (pintype "passive"))
      (node (ref "R13") (pin "1") (pinfunction "1_1") (pintype "passive"))
      (node (ref "R14") (pin "2") (pinfunction "2_2") (pintype "passive"))
      (node (ref "U$5") (pin "P$1") (pinfunction "FBX_P$1") (pintype "bidirectional"))
    )
    (net (code "75") (name "Net-(U$5-INT_VCC)") (class "Default")
      (node (ref "C24") (pin "1") (pinfunction "1_1") (pintype "passive"))
      (node (ref "U$5") (pin "P$7") (pinfunction "INT_VCC_P$7") (pintype "bidirectional"))
    )
    (net (code "76") (name "Net-(U$10-PadSBWTCK)") (class "Default")
      (node (ref "U$10") (pin "SBWTCK") (pinfunction "SBWTCK_SBWTCK") (pintype "bidirectional"))
      (node (ref "U$11") (pin "SBWTCK") (pinfunction "SBWTCK_SBWTCK") (pintype "bidirectional"))
    )
    (net (code "77") (name "Net-(U$11-P2.0_TXD)") (class "Default")
      (node (ref "U$10") (pin "P2.0_TXD") (pinfunction "P2.0_TXD_P2.0_TXD") (pintype "bidirectional"))
      (node (ref "U$11") (pin "3") (pinfunction "P2.0_TXD_3") (pintype "bidirectional"))
    )
    (net (code "78") (name "Net-(U$11-P2.1_RXD)") (class "Default")
      (node (ref "U$10") (pin "P2.1_RXD") (pinfunction "P2.1_RXD_P2.1_RXD") (pintype "bidirectional"))
      (node (ref "U$11") (pin "4") (pinfunction "P2.1_RXD_4") (pintype "bidirectional"))
    )
    (net (code "79") (name "Net-(U$11-P3.4_GPIO_DEBUG)") (class "Default")
      (node (ref "U$10") (pin "P3.4_GPIO_DEBUG") (pinfunction "P3.4_GPIO_DEBUG_P3.4_GPIO_DEBUG") (pintype "bidirectional"))
      (node (ref "U$11") (pin "7") (pinfunction "P3.4_GPIO_DEBUG_7") (pintype "bidirectional"))
    )
    (net (code "80") (name "Net-(U$11-P3.5_GPIO_DEBUG)") (class "Default")
      (node (ref "U$10") (pin "P3.5_GPIO_DEBUG") (pinfunction "P3.5_GPIO_DEBUG_P3.5_GPIO_DEBUG") (pintype "bidirectional"))
      (node (ref "U$11") (pin "8") (pinfunction "P3.5_GPIO_DEBUG_8") (pintype "bidirectional"))
    )
    (net (code "81") (name "Net-(U$11-SBWTDIO)") (class "Default")
      (node (ref "U$10") (pin "SBWTDIO") (pinfunction "SBWTDIO_SBWTDIO") (pintype "bidirectional"))
      (node (ref "U$11") (pin "2") (pinfunction "SBWTDIO_2") (pintype "bidirectional"))
    )
    (net (code "82") (name "Net-(U$13-PadSBWTCK)") (class "Default")
      (node (ref "U$13") (pin "SBWTCK") (pinfunction "SBWTCK_SBWTCK") (pintype "bidirectional"))
      (node (ref "U$14") (pin "SBWTCK") (pinfunction "SBWTCK_SBWTCK") (pintype "bidirectional"))
    )
    (net (code "83") (name "Net-(U$14-P2.0_TXD)") (class "Default")
      (node (ref "U$13") (pin "P2.0_TXD") (pinfunction "P2.0_TXD_P2.0_TXD") (pintype "bidirectional"))
      (node (ref "U$14") (pin "3") (pinfunction "P2.0_TXD_3") (pintype "bidirectional"))
    )
    (net (code "84") (name "Net-(U$14-P2.1_RXD)") (class "Default")
      (node (ref "U$13") (pin "P2.1_RXD") (pinfunction "P2.1_RXD_P2.1_RXD") (pintype "bidirectional"))
      (node (ref "U$14") (pin "4") (pinfunction "P2.1_RXD_4") (pintype "bidirectional"))
    )
    (net (code "85") (name "Net-(U$14-P3.4_GPIO_DEBUG)") (class "Default")
      (node (ref "U$13") (pin "P3.4_GPIO_DEBUG") (pinfunction "P3.4_GPIO_DEBUG_P3.4_GPIO_DEBUG") (pintype "bidirectional"))
      (node (ref "U$14") (pin "7") (pinfunction "P3.4_GPIO_DEBUG_7") (pintype "bidirectional"))
    )
    (net (code "86") (name "Net-(U$14-P3.5_GPIO_DEBUG)") (class "Default")
      (node (ref "U$13") (pin "P3.5_GPIO_DEBUG") (pinfunction "P3.5_GPIO_DEBUG_P3.5_GPIO_DEBUG") (pintype "bidirectional"))
      (node (ref "U$14") (pin "8") (pinfunction "P3.5_GPIO_DEBUG_8") (pintype "bidirectional"))
    )
    (net (code "87") (name "Net-(U$14-SBWTDIO)") (class "Default")
      (node (ref "U$13") (pin "SBWTDIO") (pinfunction "SBWTDIO_SBWTDIO") (pintype "bidirectional"))
      (node (ref "U$14") (pin "2") (pinfunction "SBWTDIO_2") (pintype "bidirectional"))
    )
    (net (code "88") (name "PWM_X") (class "Default")
      (node (ref "U$3") (pin "P1.7_GPIO/PWM") (pinfunction "P1.7_GPIO/PWM_P1.7_GPIO/PWM") (pintype "bidirectional"))
      (node (ref "U$7") (pin "PWM") (pinfunction "PWM_PWM") (pintype "bidirectional"))
    )
    (net (code "89") (name "PWM_Y") (class "Default")
      (node (ref "U$10") (pin "P1.7_GPIO/PWM") (pinfunction "P1.7_GPIO/PWM_P1.7_GPIO/PWM") (pintype "bidirectional"))
      (node (ref "U$12") (pin "PWM") (pinfunction "PWM_PWM") (pintype "bidirectional"))
    )
    (net (code "90") (name "PWM_Z") (class "Default")
      (node (ref "U$13") (pin "P1.7_GPIO/PWM") (pinfunction "P1.7_GPIO/PWM_P1.7_GPIO/PWM") (pintype "bidirectional"))
      (node (ref "U$15") (pin "PWM") (pinfunction "PWM_PWM") (pintype "bidirectional"))
    )
    (net (code "91") (name "RD_X") (class "Default")
      (node (ref "R1") (pin "1") (pinfunction "1_1") (pintype "passive"))
      (node (ref "U$3") (pin "P4.0_GPIO") (pinfunction "P4.0_GPIO_P4.0_GPIO") (pintype "bidirectional"))
      (node (ref "U$7") (pin "RD") (pinfunction "RD_RD") (pintype "bidirectional"))
    )
    (net (code "92") (name "RD_Y") (class "Default")
      (node (ref "R17") (pin "1") (pinfunction "1_1") (pintype "passive"))
      (node (ref "U$10") (pin "P4.0_GPIO") (pinfunction "P4.0_GPIO_P4.0_GPIO") (pintype "bidirectional"))
      (node (ref "U$12") (pin "RD") (pinfunction "RD_RD") (pintype "bidirectional"))
    )
    (net (code "93") (name "RD_Z") (class "Default")
      (node (ref "R25") (pin "1") (pinfunction "1_1") (pintype "passive"))
      (node (ref "U$13") (pin "P4.0_GPIO") (pinfunction "P4.0_GPIO_P4.0_GPIO") (pintype "bidirectional"))
      (node (ref "U$15") (pin "RD") (pinfunction "RD_RD") (pintype "bidirectional"))
    )
    (net (code "94") (name "SYNC1") (class "Default")
      (node (ref "U$10") (pin "P7.2_SYNC1") (pinfunction "P7.2_SYNC1_P7.2_SYNC1") (pintype "bidirectional"))
      (node (ref "U$13") (pin "P7.2_SYNC1") (pinfunction "P7.2_SYNC1_P7.2_SYNC1") (pintype "bidirectional"))
      (node (ref "U$2") (pin "P$45") (pinfunction "SYNC1_P$45") (pintype "bidirectional"))
      (node (ref "U$3") (pin "P7.2_SYNC1") (pinfunction "P7.2_SYNC1_P7.2_SYNC1") (pintype "bidirectional"))
    )
    (net (code "95") (name "SYNC2") (class "Default")
      (node (ref "U$10") (pin "PJ.3_SYNC2") (pinfunction "PJ.3_SYNC2_PJ.3_SYNC2") (pintype "bidirectional"))
      (node (ref "U$13") (pin "PJ.3_SYNC2") (pinfunction "PJ.3_SYNC2_PJ.3_SYNC2") (pintype "bidirectional"))
      (node (ref "U$2") (pin "P$49") (pinfunction "SYNC2_P$49") (pintype "bidirectional"))
      (node (ref "U$3") (pin "PJ.3_SYNC2") (pinfunction "PJ.3_SYNC2_PJ.3_SYNC2") (pintype "bidirectional"))
    )
    (net (code "96") (name "VBAT") (class "Default")
      (node (ref "C23") (pin "1") (pinfunction "1_1") (pintype "passive"))
      (node (ref "C6") (pin "2") (pinfunction "2_2") (pintype "passive"))
      (node (ref "C7") (pin "2") (pinfunction "2_2") (pintype "passive"))
      (node (ref "L2") (pin "P$4") (pinfunction "2B_P$4") (pintype "bidirectional"))
      (node (ref "LDO_3V3") (pin "P$1") (pinfunction "IN_P$1") (pintype "bidirectional"))
      (node (ref "LDO_3V3") (pin "P$3") (pinfunction "EN_P$3") (pintype "bidirectional"))
      (node (ref "LDO_5V") (pin "P$1") (pinfunction "IN_P$1") (pintype "bidirectional"))
      (node (ref "LDO_5V") (pin "P$3") (pinfunction "EN_P$3") (pintype "bidirectional"))
      (node (ref "R12") (pin "1") (pinfunction "1_1") (pintype "passive"))
      (node (ref "U$2") (pin "P$81") (pinfunction "BDOT_5V_P$81") (pintype "bidirectional"))
      (node (ref "U$2") (pin "P$83") (pinfunction "BDOT_3.3V_P$83") (pintype "bidirectional"))
      (node (ref "U$5") (pin "P$6") (pinfunction "V_IN_P$6") (pintype "bidirectional"))
    )
    (net (code "97") (name "VINT_X") (class "Default")
      (node (ref "C4") (pin "2") (pinfunction "2_2") (pintype "passive"))
      (node (ref "CMTMOD_X") (pin "P$3") (pinfunction "VCC_P$3") (pintype "bidirectional"))
      (node (ref "DAA_X") (pin "P$3") (pinfunction "VCC_P$3") (pintype "bidirectional"))
      (node (ref "MOTOR_X") (pin "P$5") (pinfunction "P$5_P$5") (pintype "bidirectional"))
      (node (ref "R1") (pin "2") (pinfunction "2_2") (pintype "passive"))
      (node (ref "R3") (pin "2") (pinfunction "2_2") (pintype "passive"))
      (node (ref "R4") (pin "1") (pinfunction "1_1") (pintype "passive"))
      (node (ref "R5") (pin "1") (pinfunction "1_1") (pintype "passive"))
      (node (ref "R6") (pin "1") (pinfunction "1_1") (pintype "passive"))
      (node (ref "R8") (pin "1") (pinfunction "1_1") (pintype "passive"))
      (node (ref "U$7") (pin "VINT") (pinfunction "VINT_VINT") (pintype "bidirectional"))
    )
    (net (code "98") (name "VINT_Y") (class "Default")
      (node (ref "C14") (pin "2") (pinfunction "2_2") (pintype "passive"))
      (node (ref "CMTMOD_Y") (pin "P$3") (pinfunction "VCC_P$3") (pintype "bidirectional"))
      (node (ref "DAA_Y") (pin "P$3") (pinfunction "VCC_P$3") (pintype "bidirectional"))
      (node (ref "MOTOR_Y") (pin "P$5") (pinfunction "P$5_P$5") (pintype "bidirectional"))
      (node (ref "R17") (pin "2") (pinfunction "2_2") (pintype "passive"))
      (node (ref "R19") (pin "2") (pinfunction "2_2") (pintype "passive"))
      (node (ref "R20") (pin "1") (pinfunction "1_1") (pintype "passive"))
      (node (ref "R21") (pin "1") (pinfunction "1_1") (pintype "passive"))
      (node (ref "R22") (pin "1") (pinfunction "1_1") (pintype "passive"))
      (node (ref "R24") (pin "1") (pinfunction "1_1") (pintype "passive"))
      (node (ref "U$12") (pin "VINT") (pinfunction "VINT_VINT") (pintype "bidirectional"))
    )
    (net (code "99") (name "VINT_Z") (class "Default")
      (node (ref "C21") (pin "2") (pinfunction "2_2") (pintype "passive"))
      (node (ref "CMTMOD_Z") (pin "P$3") (pinfunction "VCC_P$3") (pintype "bidirectional"))
      (node (ref "DAA_Z") (pin "P$3") (pinfunction "VCC_P$3") (pintype "bidirectional"))
      (node (ref "MOTOR_Z") (pin "P$5") (pinfunction "P$5_P$5") (pintype "bidirectional"))
      (node (ref "R25") (pin "2") (pinfunction "2_2") (pintype "passive"))
      (node (ref "R27") (pin "2") (pinfunction "2_2") (pintype "passive"))
      (node (ref "R28") (pin "1") (pinfunction "1_1") (pintype "passive"))
      (node (ref "R29") (pin "1") (pinfunction "1_1") (pintype "passive"))
      (node (ref "R30") (pin "1") (pinfunction "1_1") (pintype "passive"))
      (node (ref "R32") (pin "1") (pinfunction "1_1") (pintype "passive"))
      (node (ref "U$15") (pin "VINT") (pinfunction "VINT_VINT") (pintype "bidirectional"))
    )
    (net (code "100") (name "VM") (class "Default")
      (node (ref "C15") (pin "2") (pinfunction "2_2") (pintype "passive"))
      (node (ref "C22") (pin "2") (pinfunction "2_2") (pintype "passive"))
      (node (ref "C26") (pin "1") (pinfunction "1_1") (pintype "passive"))
      (node (ref "C27") (pin "1") (pinfunction "1_1") (pintype "passive"))
      (node (ref "C5") (pin "2") (pinfunction "2_2") (pintype "passive"))
      (node (ref "D2") (pin "P$2") (pinfunction "-_P$2") (pintype "bidirectional"))
      (node (ref "R13") (pin "2") (pinfunction "2_2") (pintype "passive"))
      (node (ref "U$12") (pin "VM") (pinfunction "VM_VM") (pintype "bidirectional"))
      (node (ref "U$15") (pin "VM") (pinfunction "VM_VM") (pintype "bidirectional"))
      (node (ref "U$7") (pin "VM") (pinfunction "VM_VM") (pintype "bidirectional"))
    )
    (net (code "101") (name "unconnected-(U$2-3.3V-PadP$54)") (class "Default")
      (node (ref "U$2") (pin "P$54") (pinfunction "3.3V_P$54") (pintype "bidirectional"))
    )
    (net (code "102") (name "unconnected-(U$2-3.3V-PadP$55)") (class "Default")
      (node (ref "U$2") (pin "P$55") (pinfunction "3.3V_P$55") (pintype "bidirectional"))
    )
    (net (code "103") (name "unconnected-(U$2-5V-PadP$50)") (class "Default")
      (node (ref "U$2") (pin "P$50") (pinfunction "5V_P$50") (pintype "bidirectional"))
    )
    (net (code "104") (name "unconnected-(U$2-5V-PadP$51)") (class "Default")
      (node (ref "U$2") (pin "P$51") (pinfunction "5V_P$51") (pintype "bidirectional"))
    )
    (net (code "105") (name "unconnected-(U$2-BDOT_GND-PadP$87)") (class "Default")
      (node (ref "U$2") (pin "P$87") (pinfunction "BDOT_GND_P$87") (pintype "bidirectional"))
    )
    (net (code "106") (name "unconnected-(U$2-BDOT_GND-PadP$88)") (class "Default")
      (node (ref "U$2") (pin "P$88") (pinfunction "BDOT_GND_P$88") (pintype "bidirectional"))
    )
    (net (code "107") (name "unconnected-(U$2-BDOT_VBAT-PadP$85)") (class "Default")
      (node (ref "U$2") (pin "P$85") (pinfunction "BDOT_VBAT_P$85") (pintype "bidirectional"))
    )
    (net (code "108") (name "unconnected-(U$2-BDOT_VBAT-PadP$86)") (class "Default")
      (node (ref "U$2") (pin "P$86") (pinfunction "BDOT_VBAT_P$86") (pintype "bidirectional"))
    )
    (net (code "109") (name "unconnected-(U$2-COM1_GND-PadP$102)") (class "Default")
      (node (ref "U$2") (pin "P$102") (pinfunction "COM1_GND_P$102") (pintype "bidirectional"))
    )
    (net (code "110") (name "unconnected-(U$2-COM1_GND-PadP$104)") (class "Default")
      (node (ref "U$2") (pin "P$104") (pinfunction "COM1_GND_P$104") (pintype "bidirectional"))
    )
    (net (code "111") (name "unconnected-(U$2-COM1_VBAT-PadP$101)") (class "Default")
      (node (ref "U$2") (pin "P$101") (pinfunction "COM1_VBAT_P$101") (pintype "bidirectional"))
    )
    (net (code "112") (name "unconnected-(U$2-COM1_VBAT-PadP$103)") (class "Default")
      (node (ref "U$2") (pin "P$103") (pinfunction "COM1_VBAT_P$103") (pintype "bidirectional"))
    )
    (net (code "113") (name "unconnected-(U$2-COM2_GND-PadP$98)") (class "Default")
      (node (ref "U$2") (pin "P$98") (pinfunction "COM2_GND_P$98") (pintype "bidirectional"))
    )
    (net (code "114") (name "unconnected-(U$2-COM2_GND-PadP$100)") (class "Default")
      (node (ref "U$2") (pin "P$100") (pinfunction "COM2_GND_P$100") (pintype "bidirectional"))
    )
    (net (code "115") (name "unconnected-(U$2-COM2_VBAT-PadP$97)") (class "Default")
      (node (ref "U$2") (pin "P$97") (pinfunction "COM2_VBAT_P$97") (pintype "bidirectional"))
    )
    (net (code "116") (name "unconnected-(U$2-COM2_VBAT-PadP$99)") (class "Default")
      (node (ref "U$2") (pin "P$99") (pinfunction "COM2_VBAT_P$99") (pintype "bidirectional"))
    )
    (net (code "117") (name "unconnected-(U$2-DISTRI_GND-PadP$17)") (class "Default")
      (node (ref "U$2") (pin "P$17") (pinfunction "DISTRI_GND_P$17") (pintype "bidirectional"))
    )
    (net (code "118") (name "unconnected-(U$2-DISTRI_GND-PadP$19)") (class "Default")
      (node (ref "U$2") (pin "P$19") (pinfunction "DISTRI_GND_P$19") (pintype "bidirectional"))
    )
    (net (code "119") (name "unconnected-(U$2-DISTRI_GND-PadP$22)") (class "Default")
      (node (ref "U$2") (pin "P$22") (pinfunction "DISTRI_GND_P$22") (pintype "bidirectional"))
    )
    (net (code "120") (name "unconnected-(U$2-DISTRI_GND-PadP$24)") (class "Default")
      (node (ref "U$2") (pin "P$24") (pinfunction "DISTRI_GND_P$24") (pintype "bidirectional"))
    )
    (net (code "121") (name "unconnected-(U$2-DISTRI_GND-PadP$25)") (class "Default")
      (node (ref "U$2") (pin "P$25") (pinfunction "DISTRI_GND_P$25") (pintype "bidirectional"))
    )
    (net (code "122") (name "unconnected-(U$2-DISTRI_GND-PadP$27)") (class "Default")
      (node (ref "U$2") (pin "P$27") (pinfunction "DISTRI_GND_P$27") (pintype "bidirectional"))
    )
    (net (code "123") (name "unconnected-(U$2-DISTRI_GND-PadP$30)") (class "Default")
      (node (ref "U$2") (pin "P$30") (pinfunction "DISTRI_GND_P$30") (pintype "bidirectional"))
    )
    (net (code "124") (name "unconnected-(U$2-DISTRI_GND-PadP$32)") (class "Default")
      (node (ref "U$2") (pin "P$32") (pinfunction "DISTRI_GND_P$32") (pintype "bidirectional"))
    )
    (net (code "125") (name "unconnected-(U$2-DISTRI_VBAT-PadP$18)") (class "Default")
      (node (ref "U$2") (pin "P$18") (pinfunction "DISTRI_VBAT_P$18") (pintype "bidirectional"))
    )
    (net (code "126") (name "unconnected-(U$2-DISTRI_VBAT-PadP$20)") (class "Default")
      (node (ref "U$2") (pin "P$20") (pinfunction "DISTRI_VBAT_P$20") (pintype "bidirectional"))
    )
    (net (code "127") (name "unconnected-(U$2-DISTRI_VBAT-PadP$21)") (class "Default")
      (node (ref "U$2") (pin "P$21") (pinfunction "DISTRI_VBAT_P$21") (pintype "bidirectional"))
    )
    (net (code "128") (name "unconnected-(U$2-DISTRI_VBAT-PadP$23)") (class "Default")
      (node (ref "U$2") (pin "P$23") (pinfunction "DISTRI_VBAT_P$23") (pintype "bidirectional"))
    )
    (net (code "129") (name "unconnected-(U$2-DISTRI_VBAT-PadP$26)") (class "Default")
      (node (ref "U$2") (pin "P$26") (pinfunction "DISTRI_VBAT_P$26") (pintype "bidirectional"))
    )
    (net (code "130") (name "unconnected-(U$2-DISTRI_VBAT-PadP$28)") (class "Default")
      (node (ref "U$2") (pin "P$28") (pinfunction "DISTRI_VBAT_P$28") (pintype "bidirectional"))
    )
    (net (code "131") (name "unconnected-(U$2-DISTRI_VBAT-PadP$29)") (class "Default")
      (node (ref "U$2") (pin "P$29") (pinfunction "DISTRI_VBAT_P$29") (pintype "bidirectional"))
    )
    (net (code "132") (name "unconnected-(U$2-DISTRI_VBAT-PadP$31)") (class "Default")
      (node (ref "U$2") (pin "P$31") (pinfunction "DISTRI_VBAT_P$31") (pintype "bidirectional"))
    )
    (net (code "133") (name "unconnected-(U$2-ESTIMAT_3.3V-PadP$75)") (class "Default")
      (node (ref "U$2") (pin "P$75") (pinfunction "ESTIMAT_3.3V_P$75") (pintype "bidirectional"))
    )
    (net (code "134") (name "unconnected-(U$2-ESTIMAT_3.3V-PadP$76)") (class "Default")
      (node (ref "U$2") (pin "P$76") (pinfunction "ESTIMAT_3.3V_P$76") (pintype "bidirectional"))
    )
    (net (code "135") (name "unconnected-(U$2-ESTIMAT_5V-PadP$73)") (class "Default")
      (node (ref "U$2") (pin "P$73") (pinfunction "ESTIMAT_5V_P$73") (pintype "bidirectional"))
    )
    (net (code "136") (name "unconnected-(U$2-ESTIMAT_5V-PadP$74)") (class "Default")
      (node (ref "U$2") (pin "P$74") (pinfunction "ESTIMAT_5V_P$74") (pintype "bidirectional"))
    )
    (net (code "137") (name "unconnected-(U$2-ESTIMAT_GND-PadP$79)") (class "Default")
      (node (ref "U$2") (pin "P$79") (pinfunction "ESTIMAT_GND_P$79") (pintype "bidirectional"))
    )
    (net (code "138") (name "unconnected-(U$2-ESTIMAT_GND-PadP$80)") (class "Default")
      (node (ref "U$2") (pin "P$80") (pinfunction "ESTIMAT_GND_P$80") (pintype "bidirectional"))
    )
    (net (code "139") (name "unconnected-(U$2-ESTIMAT_VBAT-PadP$77)") (class "Default")
      (node (ref "U$2") (pin "P$77") (pinfunction "ESTIMAT_VBAT_P$77") (pintype "bidirectional"))
    )
    (net (code "140") (name "unconnected-(U$2-ESTIMAT_VBAT-PadP$78)") (class "Default")
      (node (ref "U$2") (pin "P$78") (pinfunction "ESTIMAT_VBAT_P$78") (pintype "bidirectional"))
    )
    (net (code "141") (name "unconnected-(U$2-MCU_GND-PadP$46)") (class "Default")
      (node (ref "U$2") (pin "P$46") (pinfunction "MCU_GND_P$46") (pintype "bidirectional"))
    )
    (net (code "142") (name "unconnected-(U$2-MCU_GND-PadP$47)") (class "Default")
      (node (ref "U$2") (pin "P$47") (pinfunction "MCU_GND_P$47") (pintype "bidirectional"))
    )
    (net (code "143") (name "unconnected-(U$2-MCU_GND-PadP$58)") (class "Default")
      (node (ref "U$2") (pin "P$58") (pinfunction "MCU_GND_P$58") (pintype "bidirectional"))
    )
    (net (code "144") (name "unconnected-(U$2-MCU_GND-PadP$59)") (class "Default")
      (node (ref "U$2") (pin "P$59") (pinfunction "MCU_GND_P$59") (pintype "bidirectional"))
    )
    (net (code "145") (name "unconnected-(U$2-PPT_GND-PadP$1)") (class "Default")
      (node (ref "U$2") (pin "P$1") (pinfunction "PPT_GND_P$1") (pintype "bidirectional"))
    )
    (net (code "146") (name "unconnected-(U$2-PPT_GND-PadP$3)") (class "Default")
      (node (ref "U$2") (pin "P$3") (pinfunction "PPT_GND_P$3") (pintype "bidirectional"))
    )
    (net (code "147") (name "unconnected-(U$2-PPT_GND-PadP$6)") (class "Default")
      (node (ref "U$2") (pin "P$6") (pinfunction "PPT_GND_P$6") (pintype "bidirectional"))
    )
    (net (code "148") (name "unconnected-(U$2-PPT_GND-PadP$8)") (class "Default")
      (node (ref "U$2") (pin "P$8") (pinfunction "PPT_GND_P$8") (pintype "bidirectional"))
    )
    (net (code "149") (name "unconnected-(U$2-PPT_GND-PadP$9)") (class "Default")
      (node (ref "U$2") (pin "P$9") (pinfunction "PPT_GND_P$9") (pintype "bidirectional"))
    )
    (net (code "150") (name "unconnected-(U$2-PPT_GND-PadP$11)") (class "Default")
      (node (ref "U$2") (pin "P$11") (pinfunction "PPT_GND_P$11") (pintype "bidirectional"))
    )
    (net (code "151") (name "unconnected-(U$2-PPT_GND-PadP$14)") (class "Default")
      (node (ref "U$2") (pin "P$14") (pinfunction "PPT_GND_P$14") (pintype "bidirectional"))
    )
    (net (code "152") (name "unconnected-(U$2-PPT_GND-PadP$16)") (class "Default")
      (node (ref "U$2") (pin "P$16") (pinfunction "PPT_GND_P$16") (pintype "bidirectional"))
    )
    (net (code "153") (name "unconnected-(U$2-PPT_VBAT-PadP$2)") (class "Default")
      (node (ref "U$2") (pin "P$2") (pinfunction "PPT_VBAT_P$2") (pintype "bidirectional"))
    )
    (net (code "154") (name "unconnected-(U$2-PPT_VBAT-PadP$4)") (class "Default")
      (node (ref "U$2") (pin "P$4") (pinfunction "PPT_VBAT_P$4") (pintype "bidirectional"))
    )
    (net (code "155") (name "unconnected-(U$2-PPT_VBAT-PadP$5)") (class "Default")
      (node (ref "U$2") (pin "P$5") (pinfunction "PPT_VBAT_P$5") (pintype "bidirectional"))
    )
    (net (code "156") (name "unconnected-(U$2-PPT_VBAT-PadP$7)") (class "Default")
      (node (ref "U$2") (pin "P$7") (pinfunction "PPT_VBAT_P$7") (pintype "bidirectional"))
    )
    (net (code "157") (name "unconnected-(U$2-PPT_VBAT-PadP$10)") (class "Default")
      (node (ref "U$2") (pin "P$10") (pinfunction "PPT_VBAT_P$10") (pintype "bidirectional"))
    )
    (net (code "158") (name "unconnected-(U$2-PPT_VBAT-PadP$12)") (class "Default")
      (node (ref "U$2") (pin "P$12") (pinfunction "PPT_VBAT_P$12") (pintype "bidirectional"))
    )
    (net (code "159") (name "unconnected-(U$2-PPT_VBAT-PadP$13)") (class "Default")
      (node (ref "U$2") (pin "P$13") (pinfunction "PPT_VBAT_P$13") (pintype "bidirectional"))
    )
    (net (code "160") (name "unconnected-(U$2-PPT_VBAT-PadP$15)") (class "Default")
      (node (ref "U$2") (pin "P$15") (pinfunction "PPT_VBAT_P$15") (pintype "bidirectional"))
    )
    (net (code "161") (name "unconnected-(U$2-PadP$33)") (class "Default")
      (node (ref "U$2") (pin "P$33") (pinfunction "P$33_P$33") (pintype "bidirectional"))
    )
    (net (code "162") (name "unconnected-(U$2-PadP$34)") (class "Default")
      (node (ref "U$2") (pin "P$34") (pinfunction "P$34_P$34") (pintype "bidirectional"))
    )
    (net (code "163") (name "unconnected-(U$2-PadP$35)") (class "Default")
      (node (ref "U$2") (pin "P$35") (pinfunction "P$35_P$35") (pintype "bidirectional"))
    )
    (net (code "164") (name "unconnected-(U$2-PadP$36)") (class "Default")
      (node (ref "U$2") (pin "P$36") (pinfunction "P$36_P$36") (pintype "bidirectional"))
    )
    (net (code "165") (name "unconnected-(U$2-PadP$37)") (class "Default")
      (node (ref "U$2") (pin "P$37") (pinfunction "P$37_P$37") (pintype "bidirectional"))
    )
    (net (code "166") (name "unconnected-(U$2-PadP$38)") (class "Default")
      (node (ref "U$2") (pin "P$38") (pinfunction "P$38_P$38") (pintype "bidirectional"))
    )
    (net (code "167") (name "unconnected-(U$2-PadP$39)") (class "Default")
      (node (ref "U$2") (pin "P$39") (pinfunction "P$39_P$39") (pintype "bidirectional"))
    )
    (net (code "168") (name "unconnected-(U$2-PadP$40)") (class "Default")
      (node (ref "U$2") (pin "P$40") (pinfunction "P$40_P$40") (pintype "bidirectional"))
    )
    (net (code "169") (name "unconnected-(U$2-PadP$41)") (class "Default")
      (node (ref "U$2") (pin "P$41") (pinfunction "P$41_P$41") (pintype "bidirectional"))
    )
    (net (code "170") (name "unconnected-(U$2-PadP$42)") (class "Default")
      (node (ref "U$2") (pin "P$42") (pinfunction "P$42_P$42") (pintype "bidirectional"))
    )
    (net (code "171") (name "unconnected-(U$2-PadP$43)") (class "Default")
      (node (ref "U$2") (pin "P$43") (pinfunction "P$43_P$43") (pintype "bidirectional"))
    )
    (net (code "172") (name "unconnected-(U$2-PadP$44)") (class "Default")
      (node (ref "U$2") (pin "P$44") (pinfunction "P$44_P$44") (pintype "bidirectional"))
    )
    (net (code "173") (name "unconnected-(U$2-PadP$48)") (class "Default")
      (node (ref "U$2") (pin "P$48") (pinfunction "P$48_P$48") (pintype "bidirectional"))
    )
    (net (code "174") (name "unconnected-(U$2-PadP$52)") (class "Default")
      (node (ref "U$2") (pin "P$52") (pinfunction "P$52_P$52") (pintype "bidirectional"))
    )
    (net (code "175") (name "unconnected-(U$2-PadP$56)") (class "Default")
      (node (ref "U$2") (pin "P$56") (pinfunction "P$56_P$56") (pintype "bidirectional"))
    )
    (net (code "176") (name "unconnected-(U$2-PadP$60)") (class "Default")
      (node (ref "U$2") (pin "P$60") (pinfunction "P$60_P$60") (pintype "bidirectional"))
    )
    (net (code "177") (name "unconnected-(U$2-PadP$61)") (class "Default")
      (node (ref "U$2") (pin "P$61") (pinfunction "P$61_P$61") (pintype "bidirectional"))
    )
    (net (code "178") (name "unconnected-(U$2-PadP$62)") (class "Default")
      (node (ref "U$2") (pin "P$62") (pinfunction "P$62_P$62") (pintype "bidirectional"))
    )
    (net (code "179") (name "unconnected-(U$2-PadP$63)") (class "Default")
      (node (ref "U$2") (pin "P$63") (pinfunction "P$63_P$63") (pintype "bidirectional"))
    )
    (net (code "180") (name "unconnected-(U$2-PadP$64)") (class "Default")
      (node (ref "U$2") (pin "P$64") (pinfunction "P$64_P$64") (pintype "bidirectional"))
    )
    (net (code "181") (name "unconnected-(U$2-PadP$65)") (class "Default")
      (node (ref "U$2") (pin "P$65") (pinfunction "P$65_P$65") (pintype "bidirectional"))
    )
    (net (code "182") (name "unconnected-(U$2-PadP$66)") (class "Default")
      (node (ref "U$2") (pin "P$66") (pinfunction "P$66_P$66") (pintype "bidirectional"))
    )
    (net (code "183") (name "unconnected-(U$2-PadP$67)") (class "Default")
      (node (ref "U$2") (pin "P$67") (pinfunction "P$67_P$67") (pintype "bidirectional"))
    )
    (net (code "184") (name "unconnected-(U$2-PadP$68)") (class "Default")
      (node (ref "U$2") (pin "P$68") (pinfunction "P$68_P$68") (pintype "bidirectional"))
    )
    (net (code "185") (name "unconnected-(U$2-PadP$89)") (class "Default")
      (node (ref "U$2") (pin "P$89") (pinfunction "P$89_P$89") (pintype "bidirectional"))
    )
    (net (code "186") (name "unconnected-(U$2-PadP$90)") (class "Default")
      (node (ref "U$2") (pin "P$90") (pinfunction "P$90_P$90") (pintype "bidirectional"))
    )
    (net (code "187") (name "unconnected-(U$2-PadP$91)") (class "Default")
      (node (ref "U$2") (pin "P$91") (pinfunction "P$91_P$91") (pintype "bidirectional"))
    )
    (net (code "188") (name "unconnected-(U$2-PadP$92)") (class "Default")
      (node (ref "U$2") (pin "P$92") (pinfunction "P$92_P$92") (pintype "bidirectional"))
    )
    (net (code "189") (name "unconnected-(U$2-PadP$95)") (class "Default")
      (node (ref "U$2") (pin "P$95") (pinfunction "P$95_P$95") (pintype "bidirectional"))
    )
    (net (code "190") (name "unconnected-(U$2-PadP$96)") (class "Default")
      (node (ref "U$2") (pin "P$96") (pinfunction "P$96_P$96") (pintype "bidirectional"))
    )
    (net (code "191") (name "unconnected-(U$2-RAHS_GND-PadP$94)") (class "Default")
      (node (ref "U$2") (pin "P$94") (pinfunction "RAHS_GND_P$94") (pintype "bidirectional"))
    )
    (net (code "192") (name "unconnected-(U$2-RAHS_VBAT-PadP$93)") (class "Default")
      (node (ref "U$2") (pin "P$93") (pinfunction "RAHS_VBAT_P$93") (pintype "bidirectional"))
    )
    (net (code "193") (name "unconnected-(U$2-WHEEL_GND-PadP$71)") (class "Default")
      (node (ref "U$2") (pin "P$71") (pinfunction "WHEEL_GND_P$71") (pintype "bidirectional"))
    )
    (net (code "194") (name "unconnected-(U$2-WHEEL_GND-PadP$72)") (class "Default")
      (node (ref "U$2") (pin "P$72") (pinfunction "WHEEL_GND_P$72") (pintype "bidirectional"))
    )
    (net (code "195") (name "unconnected-(U$2-WHEEL_VBATT-PadP$69)") (class "Default")
      (node (ref "U$2") (pin "P$69") (pinfunction "WHEEL_VBATT_P$69") (pintype "bidirectional"))
    )
    (net (code "196") (name "unconnected-(U$2-WHEEL_VBATT-PadP$70)") (class "Default")
      (node (ref "U$2") (pin "P$70") (pinfunction "WHEEL_VBATT_P$70") (pintype "bidirectional"))
    )
    (net (code "197") (name "unconnected-(U$3-P2.3_SPI-CS2-PadP2.4_SPI-CS2)") (class "Default")
      (node (ref "U$3") (pin "P2.4_SPI-CS2") (pinfunction "P2.3_SPI-CS2_P2.4_SPI-CS2") (pintype "bidirectional"))
    )
    (net (code "198") (name "unconnected-(U$3-PadP1.0_A0)") (class "Default")
      (node (ref "U$3") (pin "P1.0_A0") (pinfunction "P1.0_A0_P1.0_A0") (pintype "bidirectional"))
    )
    (net (code "199") (name "unconnected-(U$3-PadP1.1_A1)") (class "Default")
      (node (ref "U$3") (pin "P1.1_A1") (pinfunction "P1.1_A1_P1.1_A1") (pintype "bidirectional"))
    )
    (net (code "200") (name "unconnected-(U$3-PadP1.2_A2)") (class "Default")
      (node (ref "U$3") (pin "P1.2_A2") (pinfunction "P1.2_A2_P1.2_A2") (pintype "bidirectional"))
    )
    (net (code "201") (name "unconnected-(U$3-PadP1.3_A3)") (class "Default")
      (node (ref "U$3") (pin "P1.3_A3") (pinfunction "P1.3_A3_P1.3_A3") (pintype "bidirectional"))
    )
    (net (code "202") (name "unconnected-(U$3-PadP1.4_A4)") (class "Default")
      (node (ref "U$3") (pin "P1.4_A4") (pinfunction "P1.4_A4_P1.4_A4") (pintype "bidirectional"))
    )
    (net (code "203") (name "unconnected-(U$3-PadP1.5_A5)") (class "Default")
      (node (ref "U$3") (pin "P1.5_A5") (pinfunction "P1.5_A5_P1.5_A5") (pintype "bidirectional"))
    )
    (net (code "204") (name "unconnected-(U$3-PadP2.2_GPIO{slash}PWM)") (class "Default")
      (node (ref "U$3") (pin "P2.2_GPIO/PWM") (pinfunction "P2.2_GPIO/PWM_P2.2_GPIO/PWM") (pintype "bidirectional"))
    )
    (net (code "205") (name "unconnected-(U$3-PadP2.7_SPI-CS3)") (class "Default")
      (node (ref "U$3") (pin "P2.7_SPI-CS3") (pinfunction "P2.7_SPI-CS3_P2.7_SPI-CS3") (pintype "bidirectional"))
    )
    (net (code "206") (name "unconnected-(U$3-PadP3.0_A12)") (class "Default")
      (node (ref "U$3") (pin "P3.0_A12") (pinfunction "P3.0_A12_P3.0_A12") (pintype "bidirectional"))
    )
    (net (code "207") (name "unconnected-(U$3-PadP3.1_A13)") (class "Default")
      (node (ref "U$3") (pin "P3.1_A13") (pinfunction "P3.1_A13_P3.1_A13") (pintype "bidirectional"))
    )
    (net (code "208") (name "unconnected-(U$3-PadP3.2_A14)") (class "Default")
      (node (ref "U$3") (pin "P3.2_A14") (pinfunction "P3.2_A14_P3.2_A14") (pintype "bidirectional"))
    )
    (net (code "209") (name "unconnected-(U$3-PadP3.3_A15)") (class "Default")
      (node (ref "U$3") (pin "P3.3_A15") (pinfunction "P3.3_A15_P3.3_A15") (pintype "bidirectional"))
    )
    (net (code "210") (name "unconnected-(U$3-PadP4.1_GPIO)") (class "Default")
      (node (ref "U$3") (pin "P4.1_GPIO") (pinfunction "P4.1_GPIO_P4.1_GPIO") (pintype "bidirectional"))
    )
    (net (code "211") (name "unconnected-(U$3-PadP4.2_GPIO)") (class "Default")
      (node (ref "U$3") (pin "P4.2_GPIO") (pinfunction "P4.2_GPIO_P4.2_GPIO") (pintype "bidirectional"))
    )
    (net (code "212") (name "unconnected-(U$3-PadP5.0_I2C-SDA-1)") (class "Default")
      (node (ref "U$3") (pin "P5.0_I2C-SDA-1") (pinfunction "P5.0_I2C-SDA-1_P5.0_I2C-SDA-1") (pintype "bidirectional"))
    )
    (net (code "213") (name "unconnected-(U$3-PadP5.1_I2C-SCL-1)") (class "Default")
      (node (ref "U$3") (pin "P5.1_I2C-SCL-1") (pinfunction "P5.1_I2C-SCL-1_P5.1_I2C-SCL-1") (pintype "bidirectional"))
    )
    (net (code "214") (name "unconnected-(U$3-PadP5.4_SPI-MOSI)") (class "Default")
      (node (ref "U$3") (pin "P5.4_SPI-MOSI") (pinfunction "P5.4_SPI-MOSI_P5.4_SPI-MOSI") (pintype "bidirectional"))
    )
    (net (code "215") (name "unconnected-(U$3-PadP5.5_SPI-MISO)") (class "Default")
      (node (ref "U$3") (pin "P5.5_SPI-MISO") (pinfunction "P5.5_SPI-MISO_P5.5_SPI-MISO") (pintype "bidirectional"))
    )
    (net (code "216") (name "unconnected-(U$3-PadP5.6_SPI-CLK)") (class "Default")
      (node (ref "U$3") (pin "P5.6_SPI-CLK") (pinfunction "P5.6_SPI-CLK_P5.6_SPI-CLK") (pintype "bidirectional"))
    )
    (net (code "217") (name "unconnected-(U$3-PadP7.0_I2C-SDA-2)") (class "Default")
      (node (ref "U$3") (pin "P7.0_I2C-SDA-2") (pinfunction "P7.0_I2C-SDA-2_P7.0_I2C-SDA-2") (pintype "bidirectional"))
    )
    (net (code "218") (name "unconnected-(U$3-PadP7.1_I2C-SCL-2)") (class "Default")
      (node (ref "U$3") (pin "P7.1_I2C-SCL-2") (pinfunction "P7.1_I2C-SCL-2_P7.1_I2C-SCL-2") (pintype "bidirectional"))
    )
    (net (code "219") (name "unconnected-(U$5-NC-PadP$2)") (class "Default")
      (node (ref "U$5") (pin "P$2") (pinfunction "NC_P$2") (pintype "bidirectional"))
    )
    (net (code "220") (name "unconnected-(U$10-P2.3_SPI-CS2-PadP2.4_SPI-CS2)") (class "Default")
      (node (ref "U$10") (pin "P2.4_SPI-CS2") (pinfunction "P2.3_SPI-CS2_P2.4_SPI-CS2") (pintype "bidirectional"))
    )
    (net (code "221") (name "unconnected-(U$10-PadP1.0_A0)") (class "Default")
      (node (ref "U$10") (pin "P1.0_A0") (pinfunction "P1.0_A0_P1.0_A0") (pintype "bidirectional"))
    )
    (net (code "222") (name "unconnected-(U$10-PadP1.1_A1)") (class "Default")
      (node (ref "U$10") (pin "P1.1_A1") (pinfunction "P1.1_A1_P1.1_A1") (pintype "bidirectional"))
    )
    (net (code "223") (name "unconnected-(U$10-PadP1.2_A2)") (class "Default")
      (node (ref "U$10") (pin "P1.2_A2") (pinfunction "P1.2_A2_P1.2_A2") (pintype "bidirectional"))
    )
    (net (code "224") (name "unconnected-(U$10-PadP1.3_A3)") (class "Default")
      (node (ref "U$10") (pin "P1.3_A3") (pinfunction "P1.3_A3_P1.3_A3") (pintype "bidirectional"))
    )
    (net (code "225") (name "unconnected-(U$10-PadP1.4_A4)") (class "Default")
      (node (ref "U$10") (pin "P1.4_A4") (pinfunction "P1.4_A4_P1.4_A4") (pintype "bidirectional"))
    )
    (net (code "226") (name "unconnected-(U$10-PadP1.5_A5)") (class "Default")
      (node (ref "U$10") (pin "P1.5_A5") (pinfunction "P1.5_A5_P1.5_A5") (pintype "bidirectional"))
    )
    (net (code "227") (name "unconnected-(U$10-PadP2.2_GPIO{slash}PWM)") (class "Default")
      (node (ref "U$10") (pin "P2.2_GPIO/PWM") (pinfunction "P2.2_GPIO/PWM_P2.2_GPIO/PWM") (pintype "bidirectional"))
    )
    (net (code "228") (name "unconnected-(U$10-PadP2.7_SPI-CS3)") (class "Default")
      (node (ref "U$10") (pin "P2.7_SPI-CS3") (pinfunction "P2.7_SPI-CS3_P2.7_SPI-CS3") (pintype "bidirectional"))
    )
    (net (code "229") (name "unconnected-(U$10-PadP3.0_A12)") (class "Default")
      (node (ref "U$10") (pin "P3.0_A12") (pinfunction "P3.0_A12_P3.0_A12") (pintype "bidirectional"))
    )
    (net (code "230") (name "unconnected-(U$10-PadP3.1_A13)") (class "Default")
      (node (ref "U$10") (pin "P3.1_A13") (pinfunction "P3.1_A13_P3.1_A13") (pintype "bidirectional"))
    )
    (net (code "231") (name "unconnected-(U$10-PadP3.2_A14)") (class "Default")
      (node (ref "U$10") (pin "P3.2_A14") (pinfunction "P3.2_A14_P3.2_A14") (pintype "bidirectional"))
    )
    (net (code "232") (name "unconnected-(U$10-PadP3.3_A15)") (class "Default")
      (node (ref "U$10") (pin "P3.3_A15") (pinfunction "P3.3_A15_P3.3_A15") (pintype "bidirectional"))
    )
    (net (code "233") (name "unconnected-(U$10-PadP4.1_GPIO)") (class "Default")
      (node (ref "U$10") (pin "P4.1_GPIO") (pinfunction "P4.1_GPIO_P4.1_GPIO") (pintype "bidirectional"))
    )
    (net (code "234") (name "unconnected-(U$10-PadP4.2_GPIO)") (class "Default")
      (node (ref "U$10") (pin "P4.2_GPIO") (pinfunction "P4.2_GPIO_P4.2_GPIO") (pintype "bidirectional"))
    )
    (net (code "235") (name "unconnected-(U$10-PadP5.0_I2C-SDA-1)") (class "Default")
      (node (ref "U$10") (pin "P5.0_I2C-SDA-1") (pinfunction "P5.0_I2C-SDA-1_P5.0_I2C-SDA-1") (pintype "bidirectional"))
    )
    (net (code "236") (name "unconnected-(U$10-PadP5.1_I2C-SCL-1)") (class "Default")
      (node (ref "U$10") (pin "P5.1_I2C-SCL-1") (pinfunction "P5.1_I2C-SCL-1_P5.1_I2C-SCL-1") (pintype "bidirectional"))
    )
    (net (code "237") (name "unconnected-(U$10-PadP5.4_SPI-MOSI)") (class "Default")
      (node (ref "U$10") (pin "P5.4_SPI-MOSI") (pinfunction "P5.4_SPI-MOSI_P5.4_SPI-MOSI") (pintype "bidirectional"))
    )
    (net (code "238") (name "unconnected-(U$10-PadP5.5_SPI-MISO)") (class "Default")
      (node (ref "U$10") (pin "P5.5_SPI-MISO") (pinfunction "P5.5_SPI-MISO_P5.5_SPI-MISO") (pintype "bidirectional"))
    )
    (net (code "239") (name "unconnected-(U$10-PadP5.6_SPI-CLK)") (class "Default")
      (node (ref "U$10") (pin "P5.6_SPI-CLK") (pinfunction "P5.6_SPI-CLK_P5.6_SPI-CLK") (pintype "bidirectional"))
    )
    (net (code "240") (name "unconnected-(U$10-PadP7.0_I2C-SDA-2)") (class "Default")
      (node (ref "U$10") (pin "P7.0_I2C-SDA-2") (pinfunction "P7.0_I2C-SDA-2_P7.0_I2C-SDA-2") (pintype "bidirectional"))
    )
    (net (code "241") (name "unconnected-(U$10-PadP7.1_I2C-SCL-2)") (class "Default")
      (node (ref "U$10") (pin "P7.1_I2C-SCL-2") (pinfunction "P7.1_I2C-SCL-2_P7.1_I2C-SCL-2") (pintype "bidirectional"))
    )
    (net (code "242") (name "unconnected-(U$13-P2.3_SPI-CS2-PadP2.4_SPI-CS2)") (class "Default")
      (node (ref "U$13") (pin "P2.4_SPI-CS2") (pinfunction "P2.3_SPI-CS2_P2.4_SPI-CS2") (pintype "bidirectional"))
    )
    (net (code "243") (name "unconnected-(U$13-PadP1.0_A0)") (class "Default")
      (node (ref "U$13") (pin "P1.0_A0") (pinfunction "P1.0_A0_P1.0_A0") (pintype "bidirectional"))
    )
    (net (code "244") (name "unconnected-(U$13-PadP1.1_A1)") (class "Default")
      (node (ref "U$13") (pin "P1.1_A1") (pinfunction "P1.1_A1_P1.1_A1") (pintype "bidirectional"))
    )
    (net (code "245") (name "unconnected-(U$13-PadP1.2_A2)") (class "Default")
      (node (ref "U$13") (pin "P1.2_A2") (pinfunction "P1.2_A2_P1.2_A2") (pintype "bidirectional"))
    )
    (net (code "246") (name "unconnected-(U$13-PadP1.3_A3)") (class "Default")
      (node (ref "U$13") (pin "P1.3_A3") (pinfunction "P1.3_A3_P1.3_A3") (pintype "bidirectional"))
    )
    (net (code "247") (name "unconnected-(U$13-PadP1.4_A4)") (class "Default")
      (node (ref "U$13") (pin "P1.4_A4") (pinfunction "P1.4_A4_P1.4_A4") (pintype "bidirectional"))
    )
    (net (code "248") (name "unconnected-(U$13-PadP1.5_A5)") (class "Default")
      (node (ref "U$13") (pin "P1.5_A5") (pinfunction "P1.5_A5_P1.5_A5") (pintype "bidirectional"))
    )
    (net (code "249") (name "unconnected-(U$13-PadP2.2_GPIO{slash}PWM)") (class "Default")
      (node (ref "U$13") (pin "P2.2_GPIO/PWM") (pinfunction "P2.2_GPIO/PWM_P2.2_GPIO/PWM") (pintype "bidirectional"))
    )
    (net (code "250") (name "unconnected-(U$13-PadP2.7_SPI-CS3)") (class "Default")
      (node (ref "U$13") (pin "P2.7_SPI-CS3") (pinfunction "P2.7_SPI-CS3_P2.7_SPI-CS3") (pintype "bidirectional"))
    )
    (net (code "251") (name "unconnected-(U$13-PadP3.0_A12)") (class "Default")
      (node (ref "U$13") (pin "P3.0_A12") (pinfunction "P3.0_A12_P3.0_A12") (pintype "bidirectional"))
    )
    (net (code "252") (name "unconnected-(U$13-PadP3.1_A13)") (class "Default")
      (node (ref "U$13") (pin "P3.1_A13") (pinfunction "P3.1_A13_P3.1_A13") (pintype "bidirectional"))
    )
    (net (code "253") (name "unconnected-(U$13-PadP3.2_A14)") (class "Default")
      (node (ref "U$13") (pin "P3.2_A14") (pinfunction "P3.2_A14_P3.2_A14") (pintype "bidirectional"))
    )
    (net (code "254") (name "unconnected-(U$13-PadP3.3_A15)") (class "Default")
      (node (ref "U$13") (pin "P3.3_A15") (pinfunction "P3.3_A15_P3.3_A15") (pintype "bidirectional"))
    )
    (net (code "255") (name "unconnected-(U$13-PadP4.1_GPIO)") (class "Default")
      (node (ref "U$13") (pin "P4.1_GPIO") (pinfunction "P4.1_GPIO_P4.1_GPIO") (pintype "bidirectional"))
    )
    (net (code "256") (name "unconnected-(U$13-PadP4.2_GPIO)") (class "Default")
      (node (ref "U$13") (pin "P4.2_GPIO") (pinfunction "P4.2_GPIO_P4.2_GPIO") (pintype "bidirectional"))
    )
    (net (code "257") (name "unconnected-(U$13-PadP5.0_I2C-SDA-1)") (class "Default")
      (node (ref "U$13") (pin "P5.0_I2C-SDA-1") (pinfunction "P5.0_I2C-SDA-1_P5.0_I2C-SDA-1") (pintype "bidirectional"))
    )
    (net (code "258") (name "unconnected-(U$13-PadP5.1_I2C-SCL-1)") (class "Default")
      (node (ref "U$13") (pin "P5.1_I2C-SCL-1") (pinfunction "P5.1_I2C-SCL-1_P5.1_I2C-SCL-1") (pintype "bidirectional"))
    )
    (net (code "259") (name "unconnected-(U$13-PadP5.4_SPI-MOSI)") (class "Default")
      (node (ref "U$13") (pin "P5.4_SPI-MOSI") (pinfunction "P5.4_SPI-MOSI_P5.4_SPI-MOSI") (pintype "bidirectional"))
    )
    (net (code "260") (name "unconnected-(U$13-PadP5.5_SPI-MISO)") (class "Default")
      (node (ref "U$13") (pin "P5.5_SPI-MISO") (pinfunction "P5.5_SPI-MISO_P5.5_SPI-MISO") (pintype "bidirectional"))
    )
    (net (code "261") (name "unconnected-(U$13-PadP5.6_SPI-CLK)") (class "Default")
      (node (ref "U$13") (pin "P5.6_SPI-CLK") (pinfunction "P5.6_SPI-CLK_P5.6_SPI-CLK") (pintype "bidirectional"))
    )
    (net (code "262") (name "unconnected-(U$13-PadP7.0_I2C-SDA-2)") (class "Default")
      (node (ref "U$13") (pin "P7.0_I2C-SDA-2") (pinfunction "P7.0_I2C-SDA-2_P7.0_I2C-SDA-2") (pintype "bidirectional"))
    )
    (net (code "263") (name "unconnected-(U$13-PadP7.1_I2C-SCL-2)") (class "Default")
      (node (ref "U$13") (pin "P7.1_I2C-SCL-2") (pinfunction "P7.1_I2C-SCL-2_P7.1_I2C-SCL-2") (pintype "bidirectional"))
    )
  )
)
